# singleBandRepeater.net
KiCad netlist of a schematic drawn in EAGLE
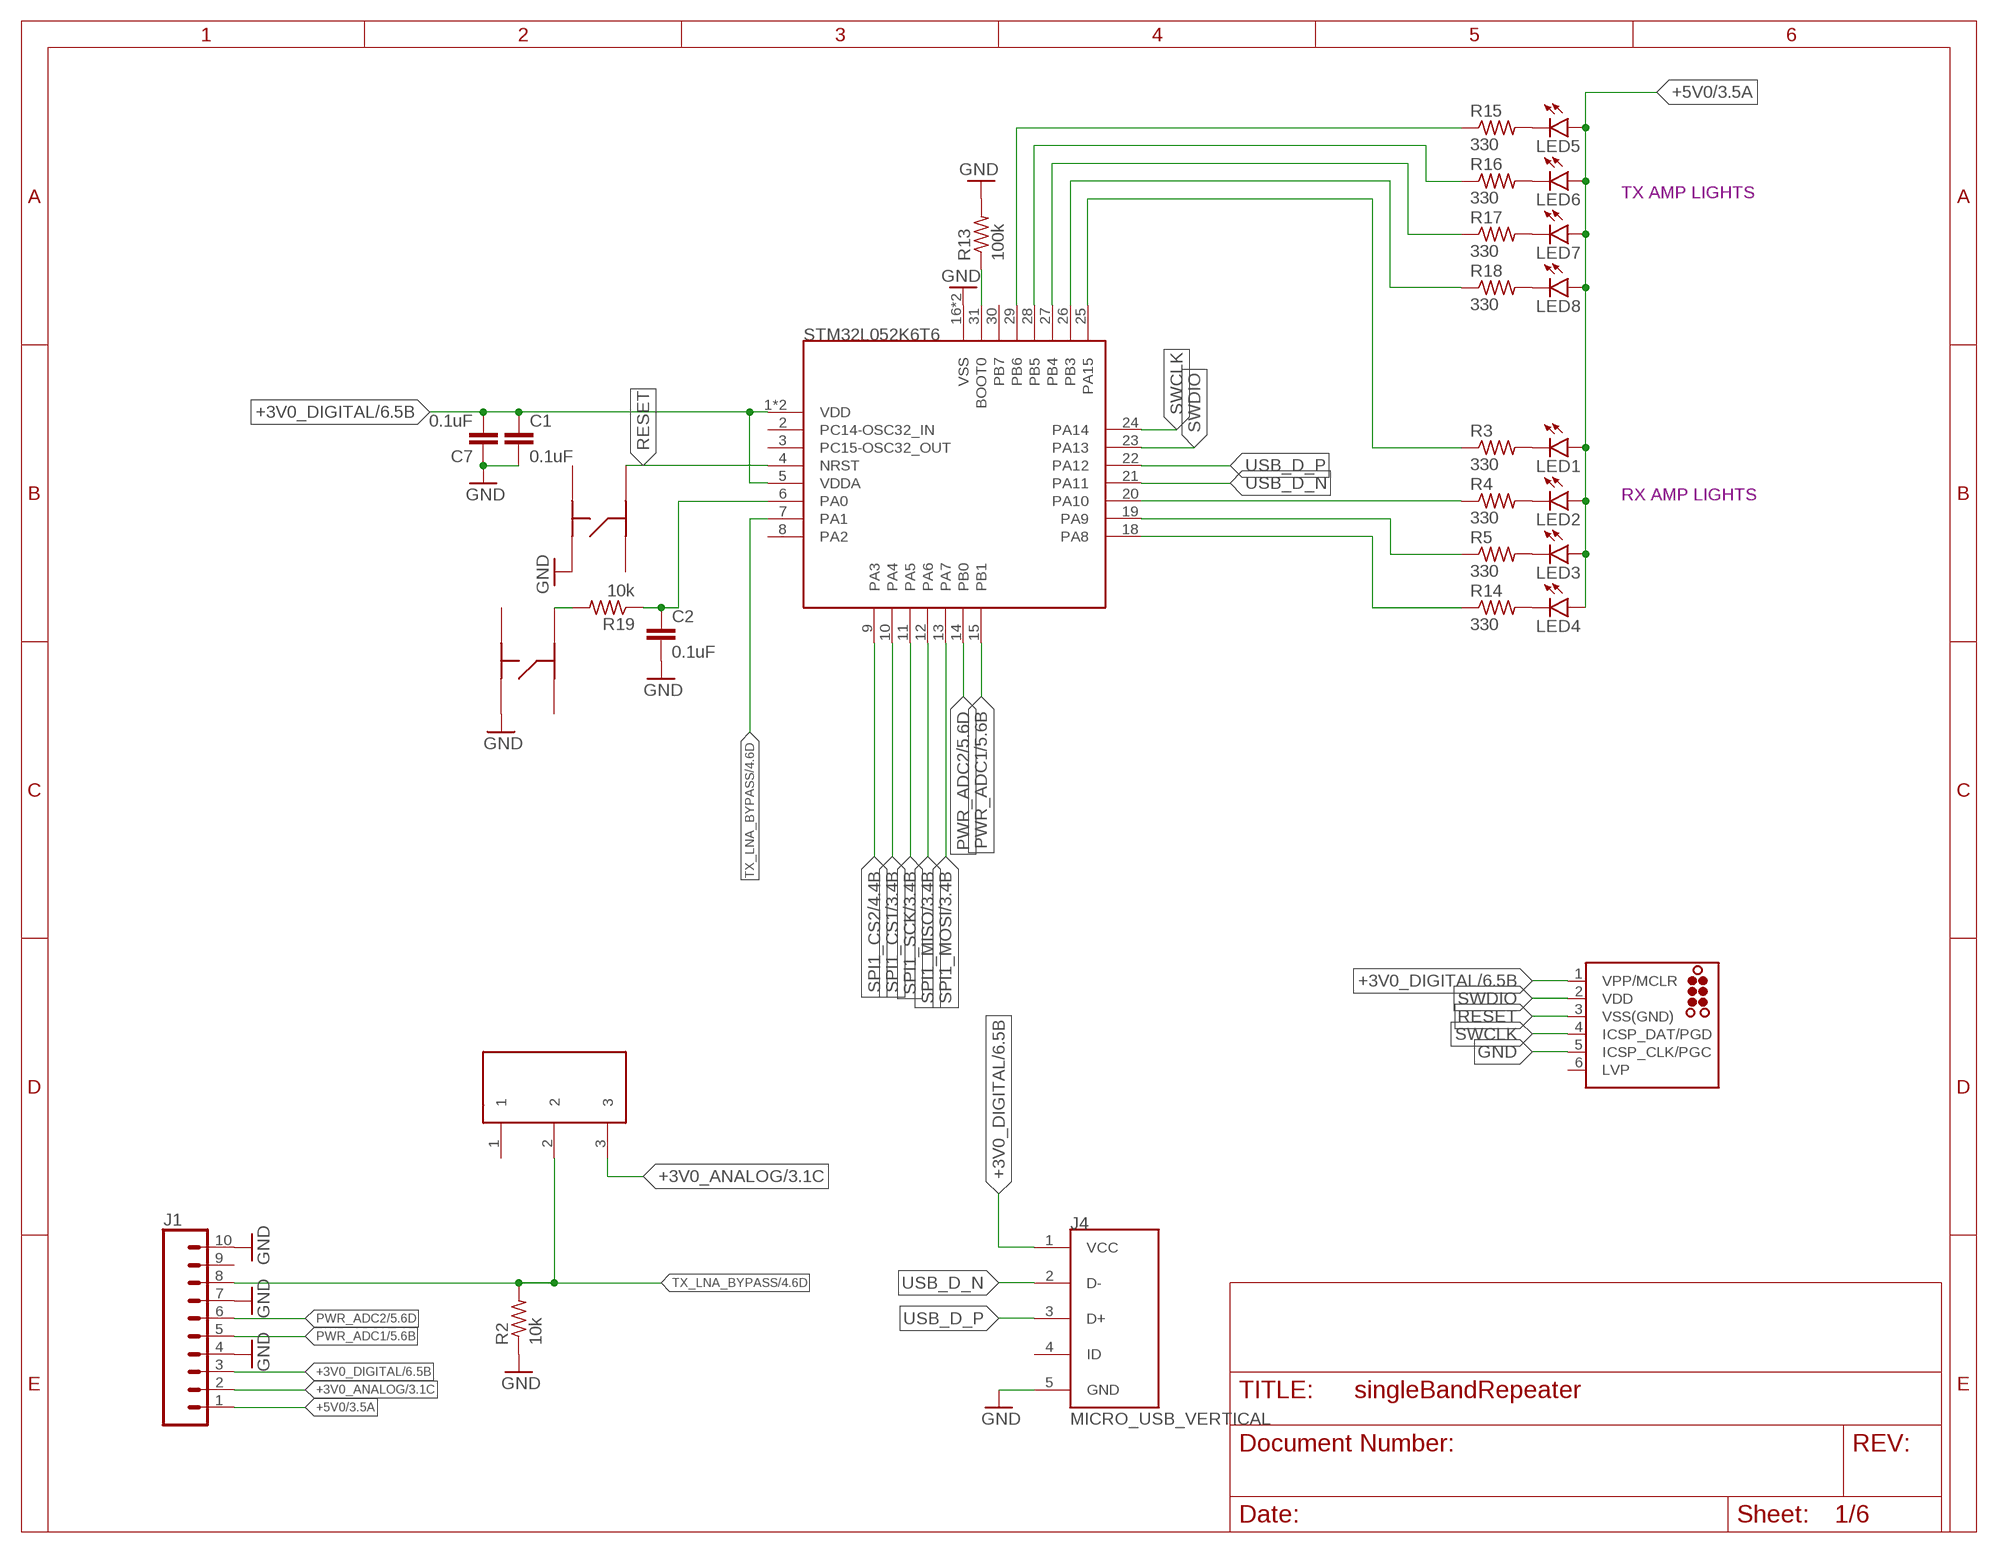
[diagram p0: schematic, sheet 1]
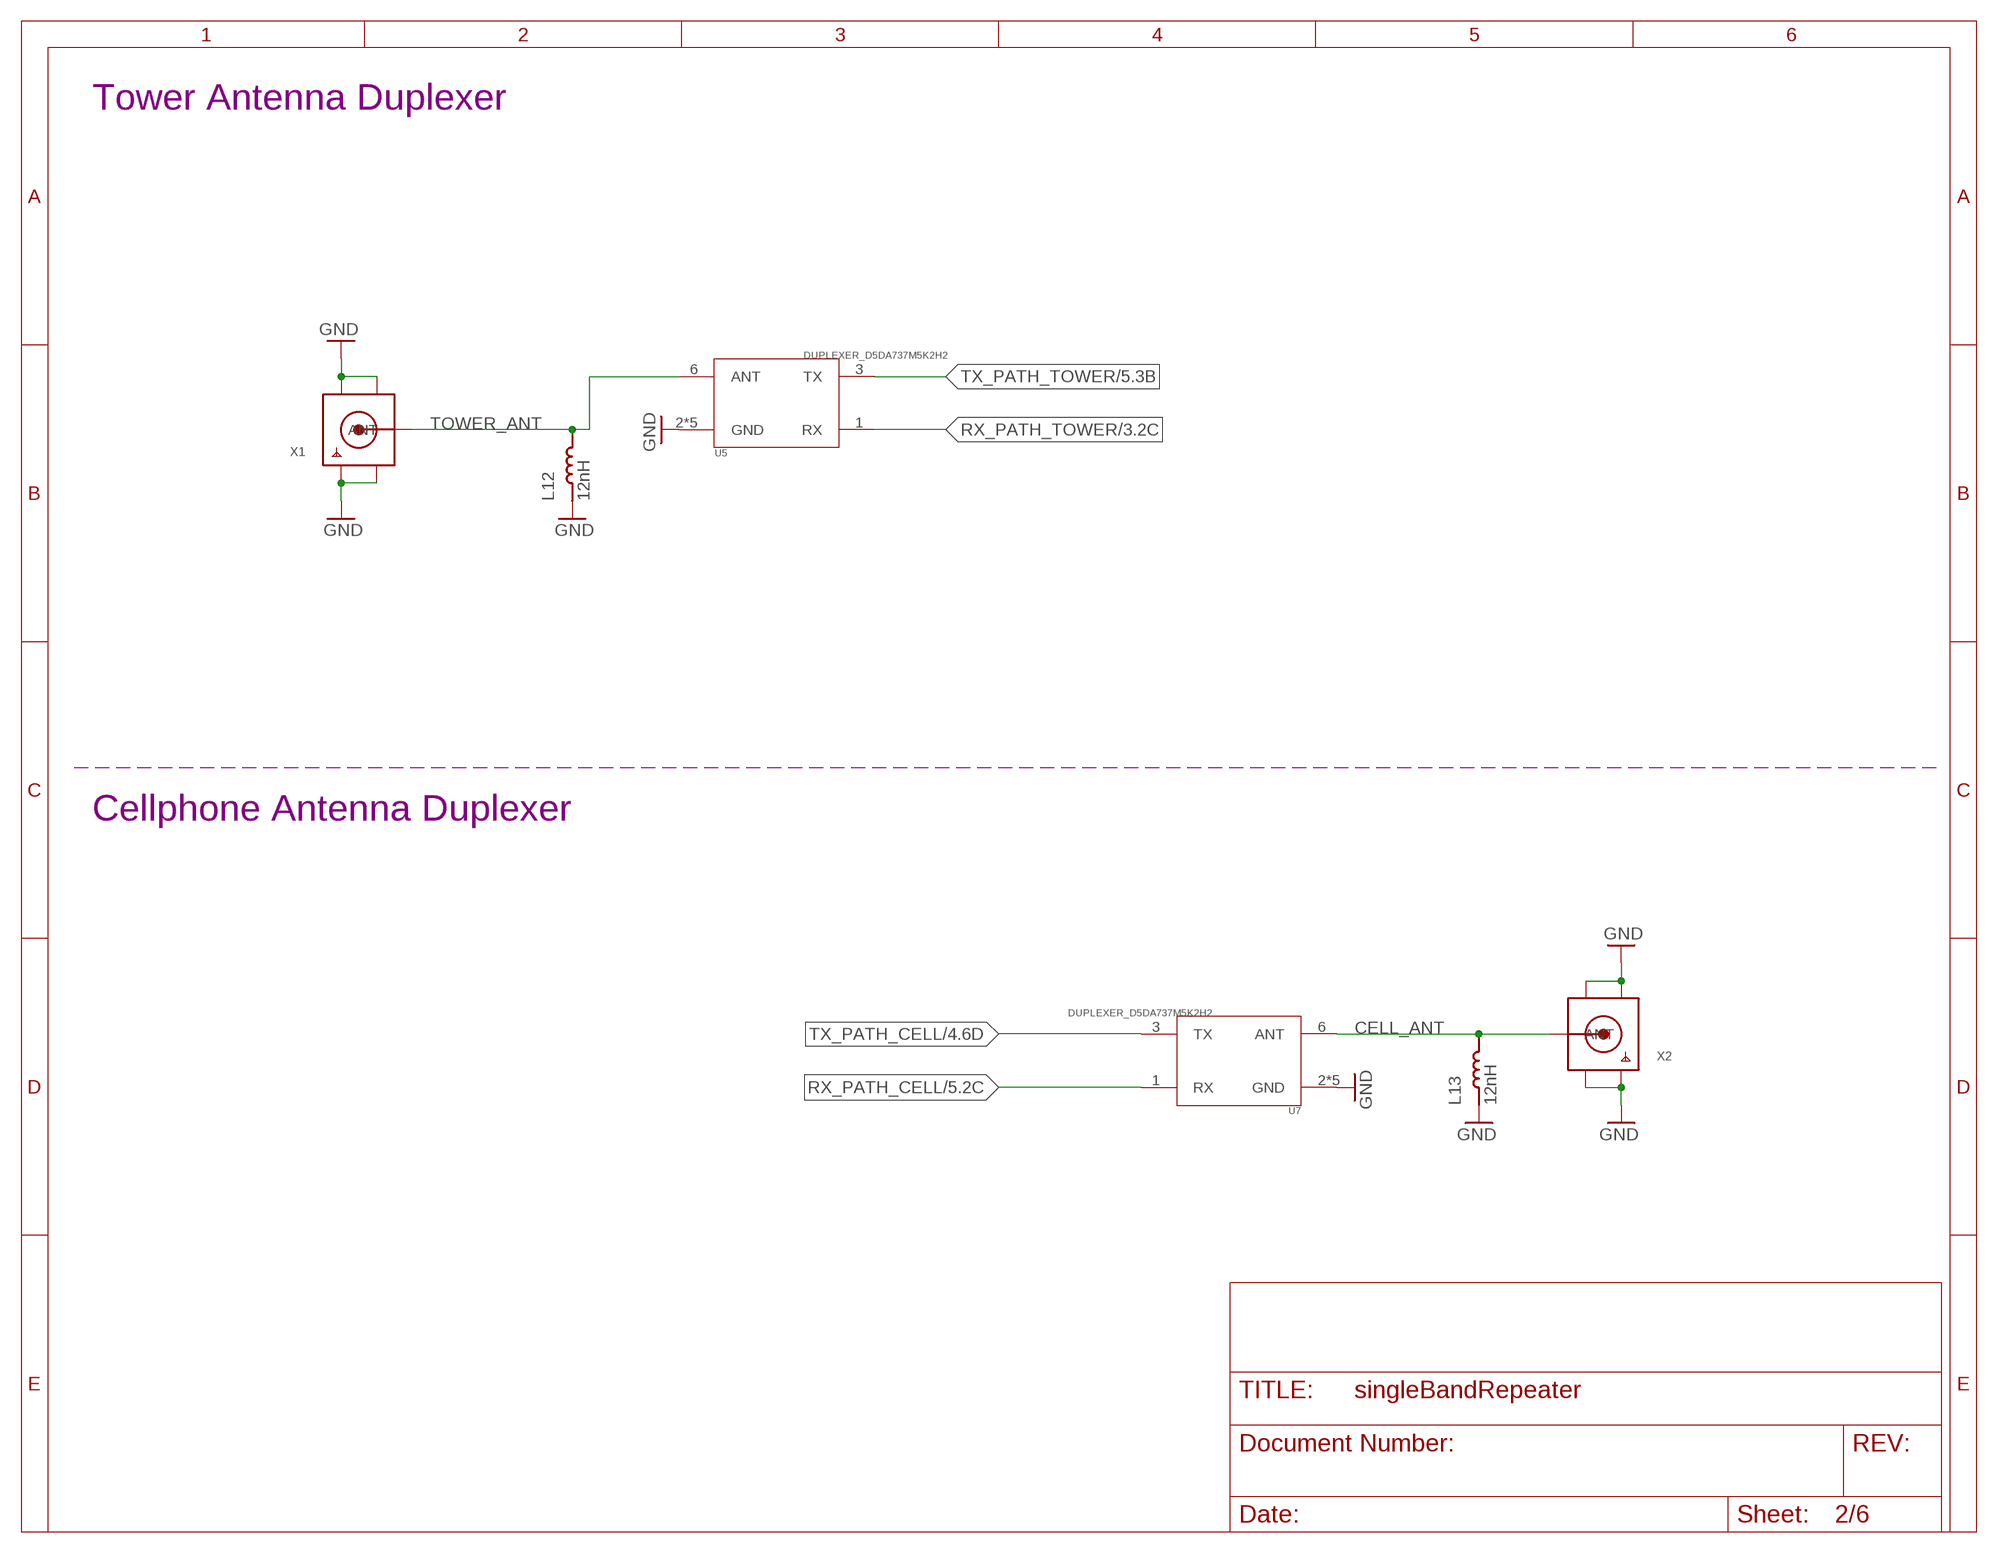
[diagram p1: schematic, sheet 2]
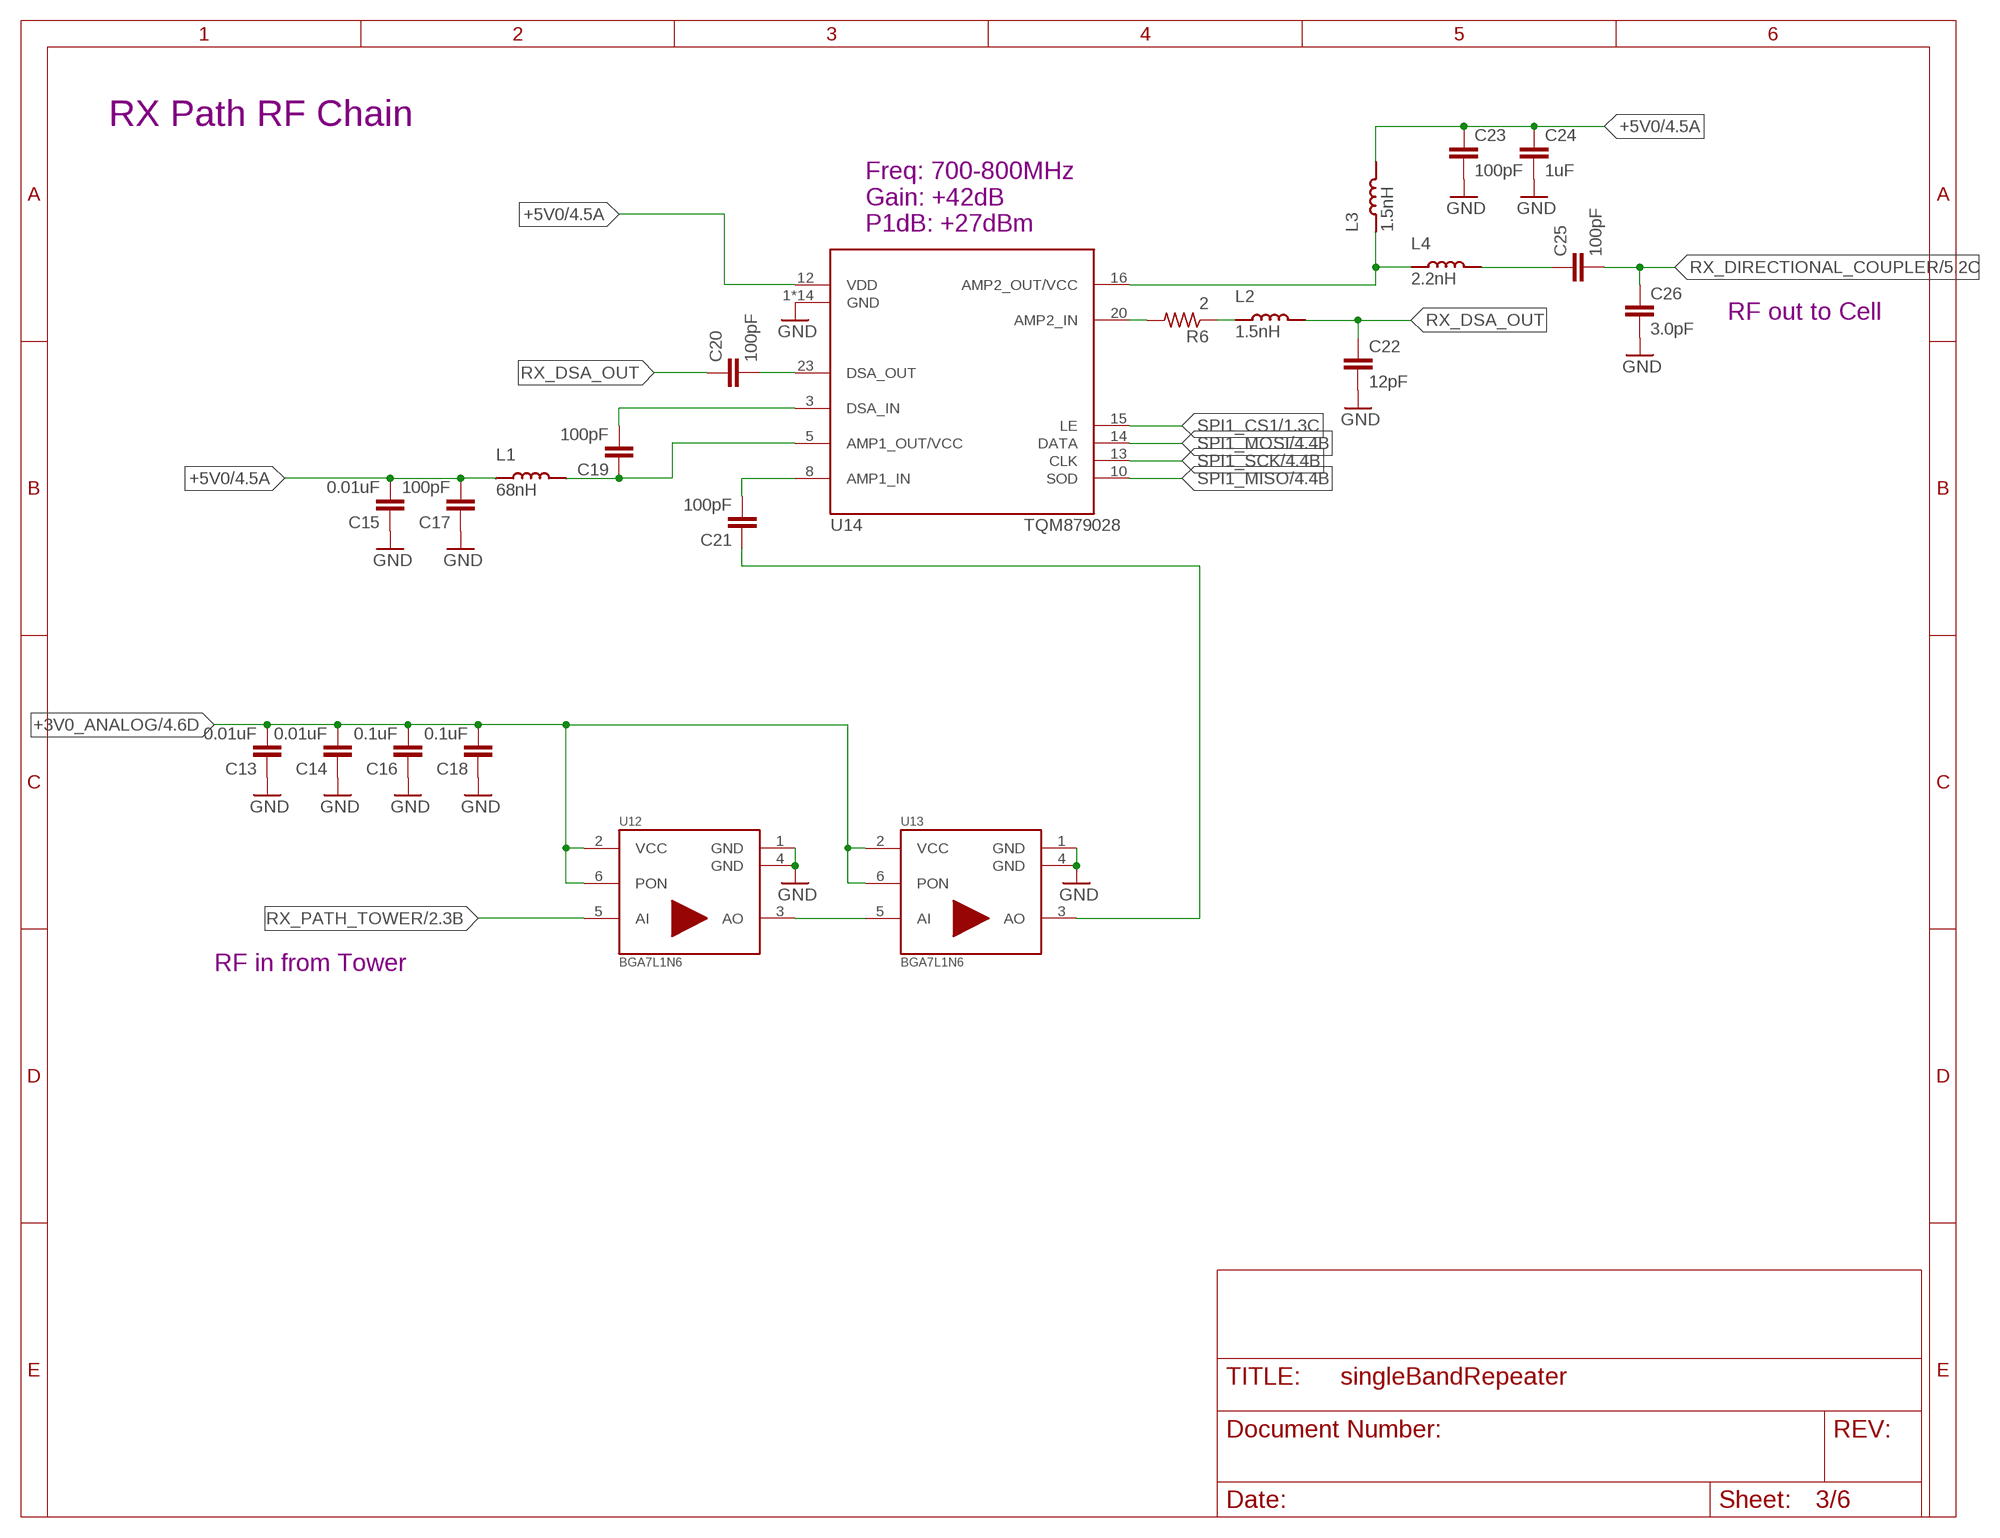
[diagram p2: schematic, sheet 3]
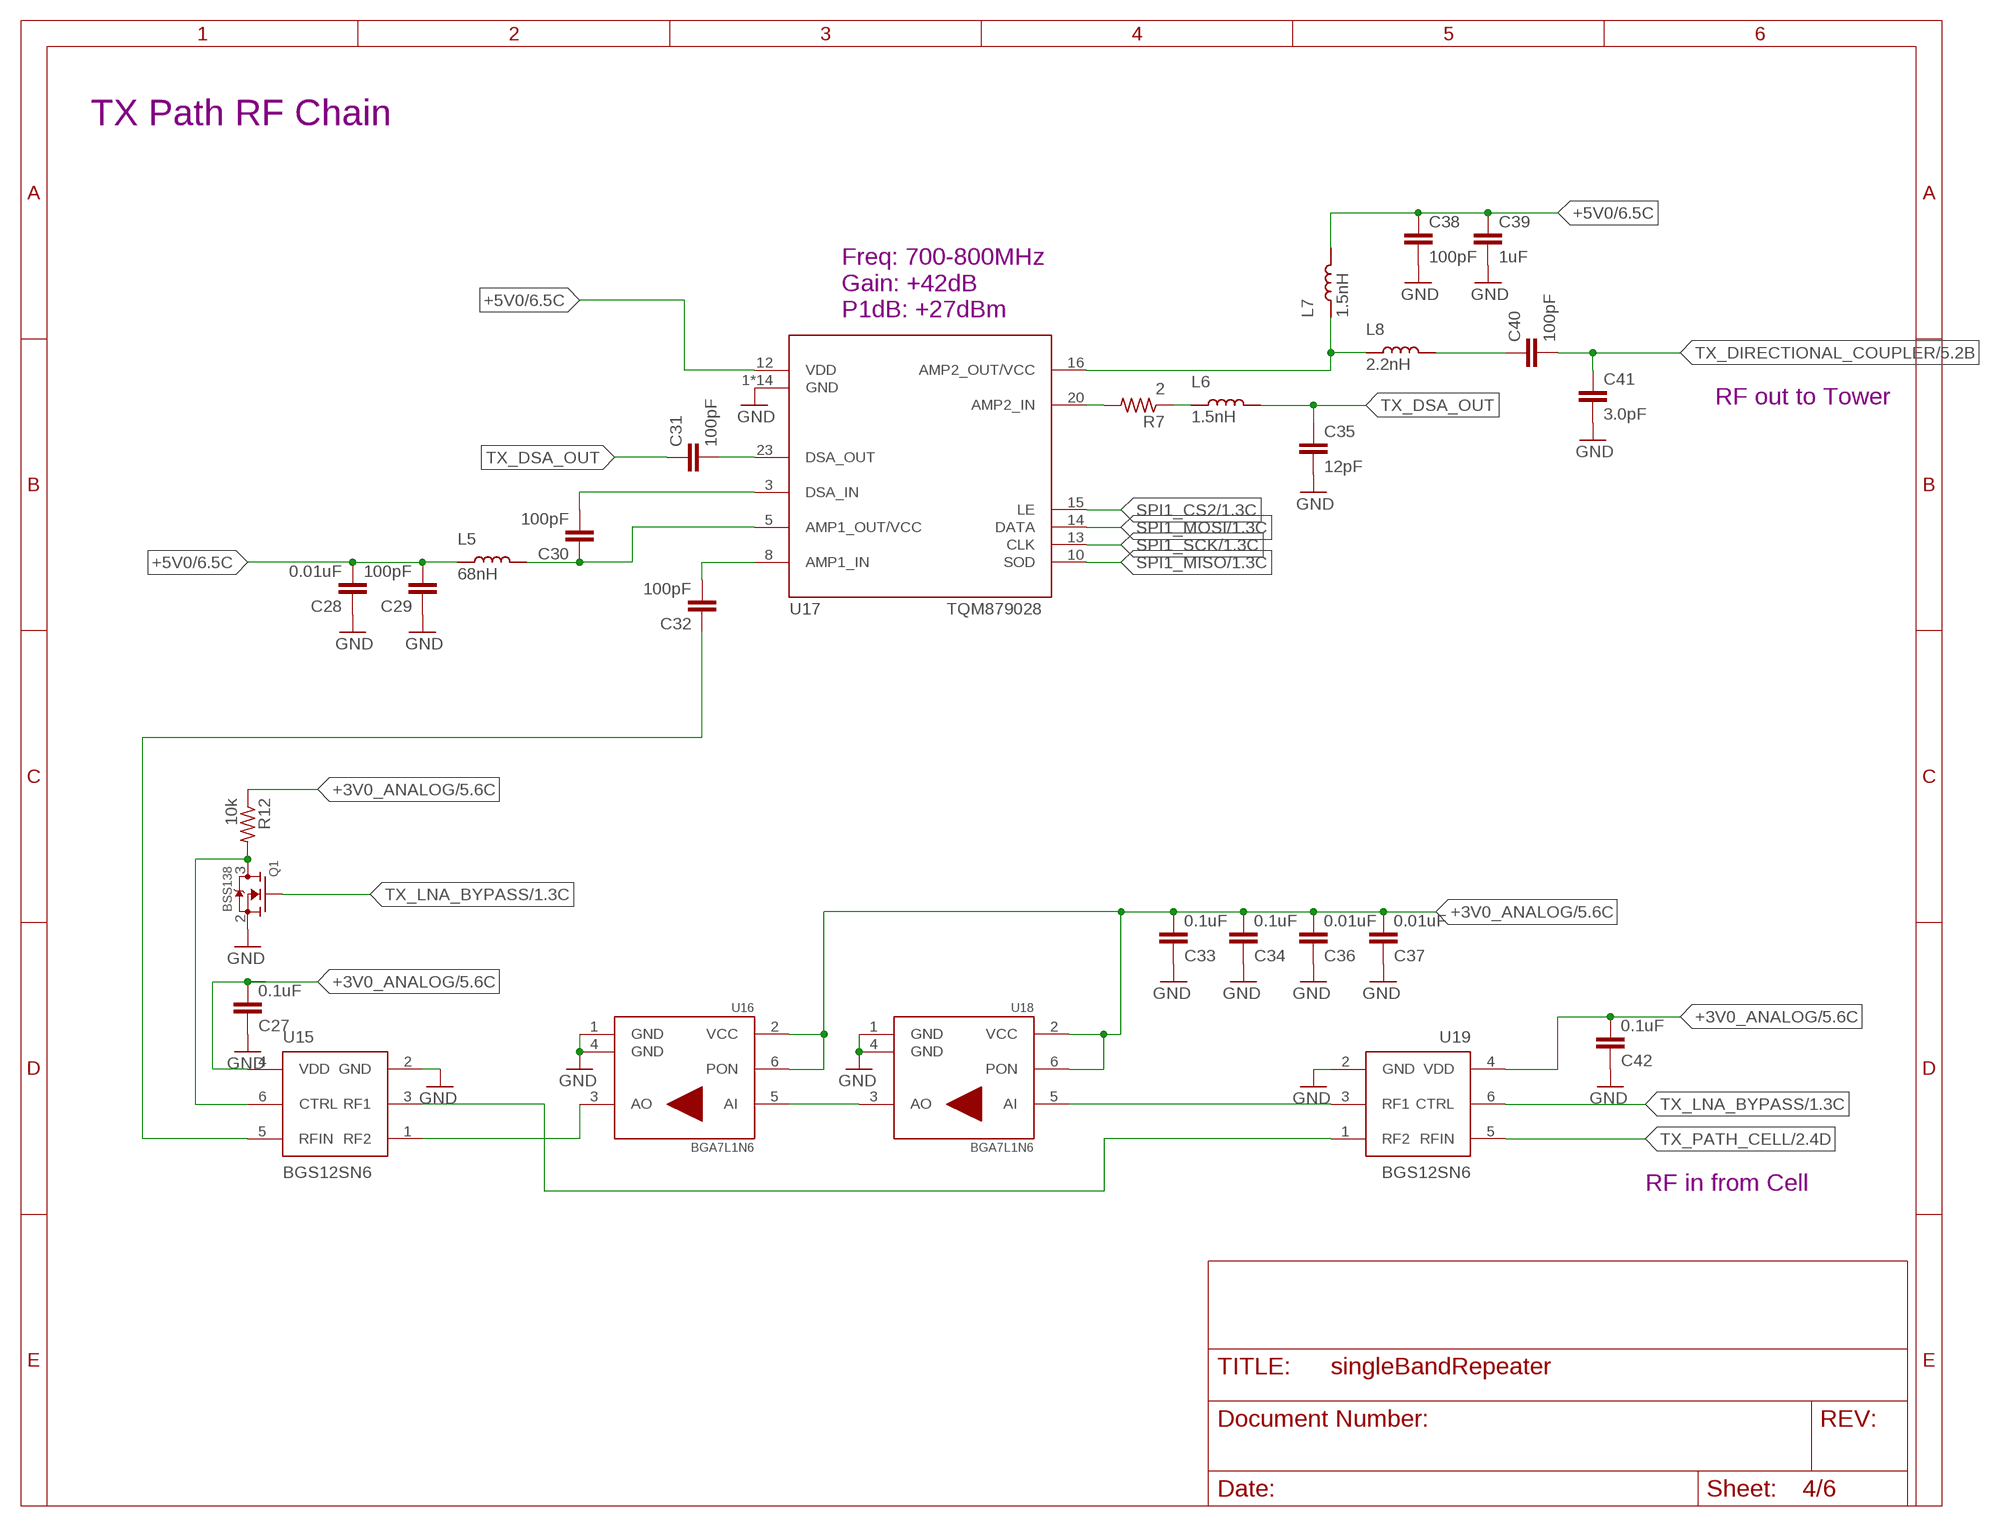
[diagram p3: schematic, sheet 4]
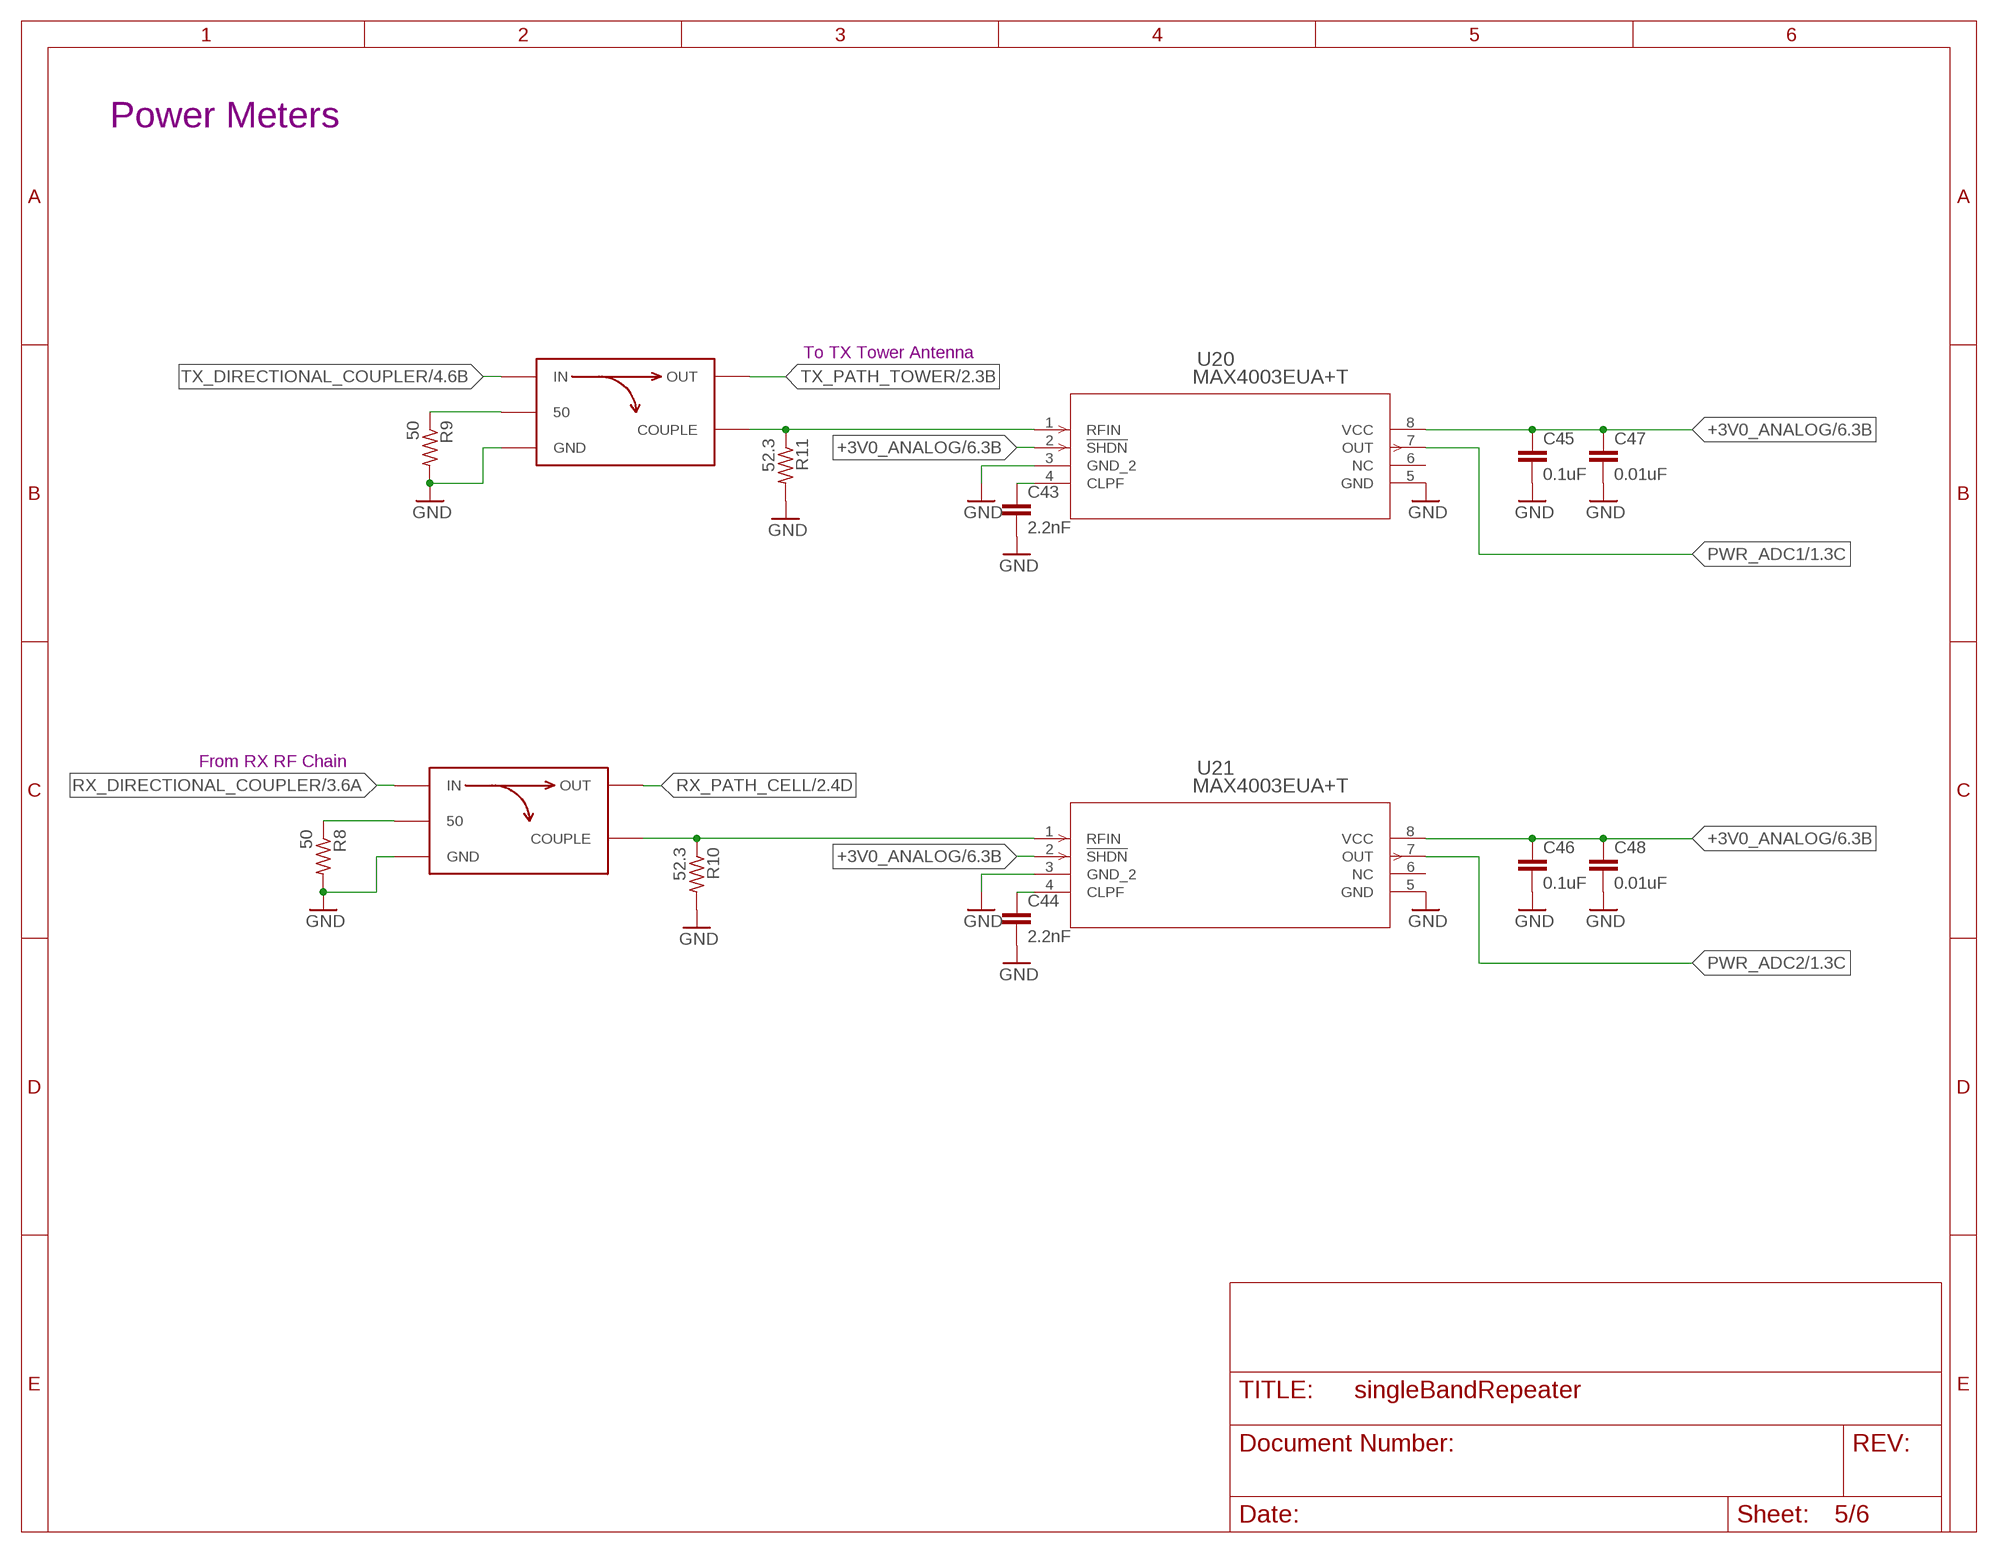
[diagram p4: schematic, sheet 5]
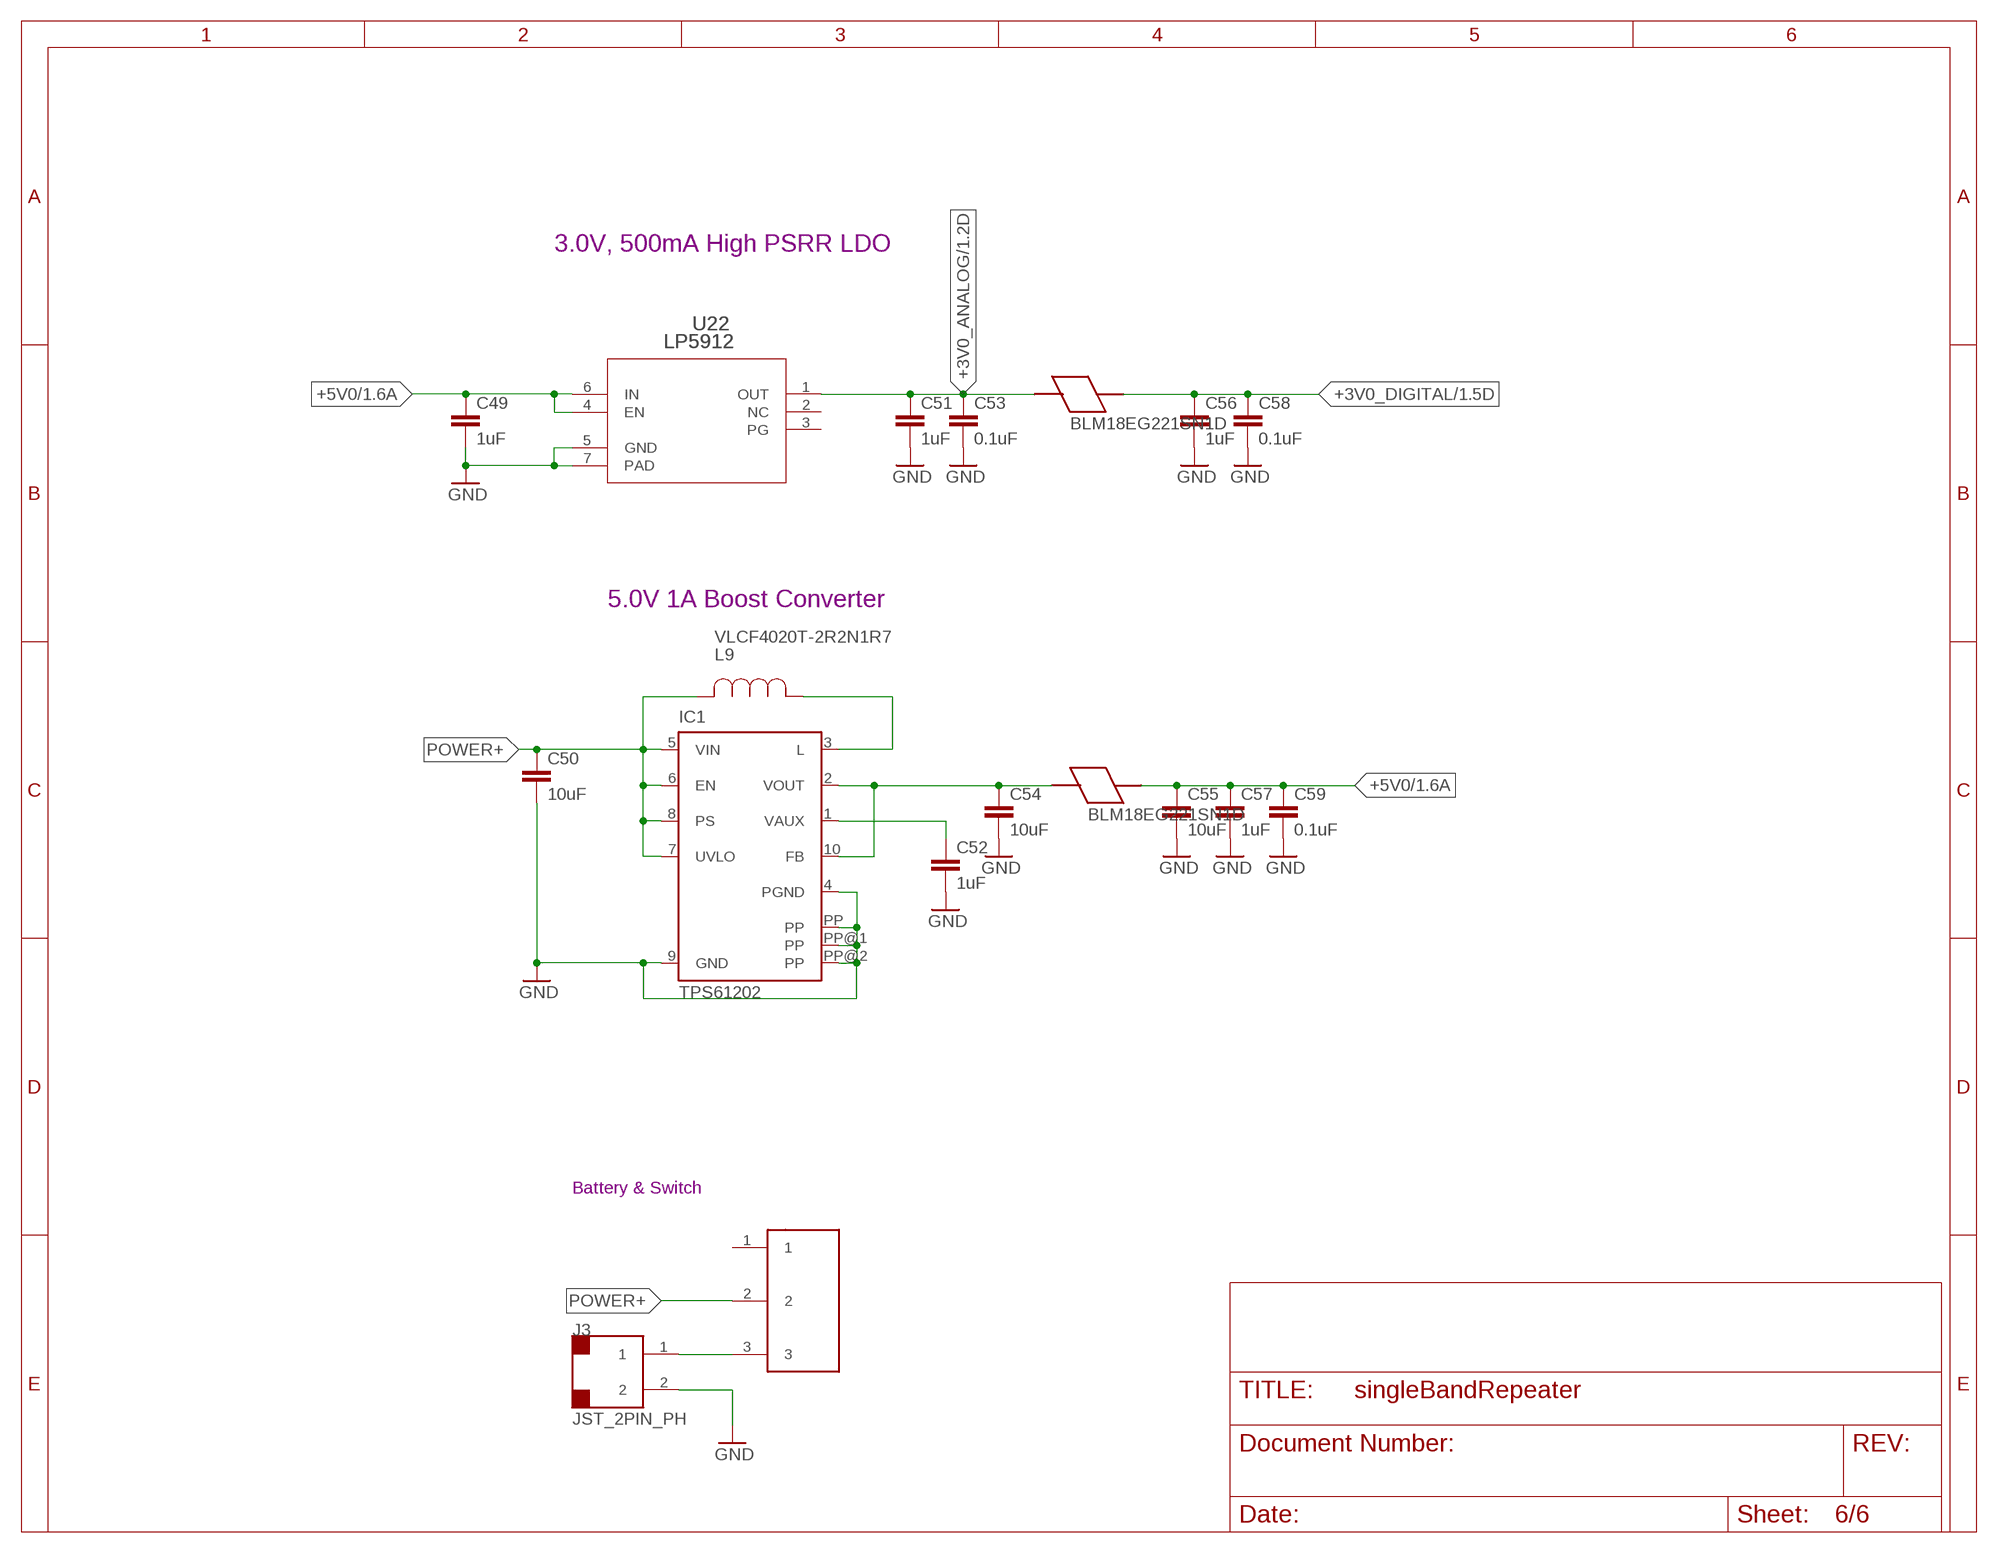
[diagram p5: schematic, sheet 6]

(export (version "E")
  (design (tool "Eeschema 10.0.6"))
  (components
    (comp (ref "C43")
      (value "2.2nF")
      (footprint "eagle-import:C0402")
      (libsource (lib "eagle-import") (part "C-EUC0402"))
    )
    (comp (ref "C44")
      (value "2.2nF")
      (footprint "eagle-import:C0402")
      (libsource (lib "eagle-import") (part "C-EUC0402"))
    )
    (comp (ref "C45")
      (value "0.1uF")
      (footprint "eagle-import:C0402")
      (libsource (lib "eagle-import") (part "C-EUC0402"))
    )
    (comp (ref "C46")
      (value "0.1uF")
      (footprint "eagle-import:C0402")
      (libsource (lib "eagle-import") (part "C-EUC0402"))
    )
    (comp (ref "C47")
      (value "0.01uF")
      (footprint "eagle-import:C0402")
      (libsource (lib "eagle-import") (part "C-EUC0402"))
    )
    (comp (ref "C48")
      (value "0.01uF")
      (footprint "eagle-import:C0402")
      (libsource (lib "eagle-import") (part "C-EUC0402"))
    )
    (comp (ref "HY1")
      (value "HHM22152A2")
      (footprint "eagle-import:HHM22152A2")
      (libsource (lib "eagle-import") (part "HHM22152A2"))
    )
    (comp (ref "HY2")
      (value "HHM22152A2")
      (footprint "eagle-import:HHM22152A2")
      (libsource (lib "eagle-import") (part "HHM22152A2"))
    )
    (comp (ref "R8")
      (value "50")
      (footprint "eagle-import:R0402")
      (libsource (lib "eagle-import") (part "R-US_R0402"))
    )
    (comp (ref "R9")
      (value "50")
      (footprint "eagle-import:R0402")
      (libsource (lib "eagle-import") (part "R-US_R0402"))
    )
    (comp (ref "R10")
      (value "52.3")
      (footprint "eagle-import:R0402")
      (libsource (lib "eagle-import") (part "R-US_R0402"))
    )
    (comp (ref "R11")
      (value "52.3")
      (footprint "eagle-import:R0402")
      (libsource (lib "eagle-import") (part "R-US_R0402"))
    )
    (comp (ref "U20")
      (value "MAX4003EUA+T")
      (footprint "eagle-import:21-0036K")
      (fields (field (name "MANUFACTURER_PART_NUMBER") "max4003eua+T"))
      (libsource (lib "eagle-import") (part "MAX4003EUA+T"))
    )
    (comp (ref "U21")
      (value "MAX4003EUA+T")
      (footprint "eagle-import:21-0036K")
      (fields (field (name "MANUFACTURER_PART_NUMBER") "max4003eua+T"))
      (libsource (lib "eagle-import") (part "MAX4003EUA+T"))
    )
    (comp (ref "L12")
      (value "12nH")
      (footprint "eagle-import:0402")
      (libsource (lib "eagle-import") (part "INDUCTOR0402"))
    )
    (comp (ref "L13")
      (value "12nH")
      (footprint "eagle-import:0402")
      (libsource (lib "eagle-import") (part "INDUCTOR0402"))
    )
    (comp (ref "U5")
      (value "DUPLEXER_D5DA737M5K2H2")
      (footprint "eagle-import:TAIYO_YUDEN_DUPLEX_1.8X1.4")
      (libsource (lib "eagle-import") (part "DUPLEXER_D5DA737M5K2H2"))
    )
    (comp (ref "U7")
      (value "DUPLEXER_D5DA737M5K2H2")
      (footprint "eagle-import:TAIYO_YUDEN_DUPLEX_1.8X1.4")
      (libsource (lib "eagle-import") (part "DUPLEXER_D5DA737M5K2H2"))
    )
    (comp (ref "X1")
      (value "SMACONNECTORSMA_DIP")
      (footprint "eagle-import:SMA_DIP")
      (libsource (lib "eagle-import") (part "SMACONNECTORSMA_DIP"))
    )
    (comp (ref "X2")
      (value "SMACONNECTORSMA_DIP")
      (footprint "eagle-import:SMA_DIP")
      (libsource (lib "eagle-import") (part "SMACONNECTORSMA_DIP"))
    )
    (comp (ref "C1")
      (value "0.1uF")
      (footprint "eagle-import:C0402")
      (libsource (lib "eagle-import") (part "C-EUC0402"))
    )
    (comp (ref "C2")
      (value "0.1uF")
      (footprint "eagle-import:C0402")
      (libsource (lib "eagle-import") (part "C-EUC0402"))
    )
    (comp (ref "C7")
      (value "0.1uF")
      (footprint "eagle-import:C0402")
      (libsource (lib "eagle-import") (part "C-EUC0402"))
    )
    (comp (ref "J1")
      (value "CONN_10\"")
      (footprint "eagle-import:1X10")
      (libsource (lib "eagle-import") (part "CONN_10{dblquote}"))
    )
    (comp (ref "J2")
      (value "TC2030-MCP")
      (footprint "eagle-import:TC2030-MCP")
      (libsource (lib "eagle-import") (part "TC2030-MCP"))
    )
    (comp (ref "J4")
      (value "MICRO_USB_VERTICAL")
      (footprint "eagle-import:MICRO_USB_VERTICAL")
      (libsource (lib "eagle-import") (part "MICRO_USB_VERTICAL"))
    )
    (comp (ref "LED1")
      (value "LEDCHIPLED_0603")
      (footprint "eagle-import:CHIPLED_0603")
      (libsource (lib "eagle-import") (part "LEDCHIPLED_0603"))
    )
    (comp (ref "LED2")
      (value "LEDCHIPLED_0603")
      (footprint "eagle-import:CHIPLED_0603")
      (libsource (lib "eagle-import") (part "LEDCHIPLED_0603"))
    )
    (comp (ref "LED3")
      (value "LEDCHIPLED_0603")
      (footprint "eagle-import:CHIPLED_0603")
      (libsource (lib "eagle-import") (part "LEDCHIPLED_0603"))
    )
    (comp (ref "LED4")
      (value "LEDCHIPLED_0603")
      (footprint "eagle-import:CHIPLED_0603")
      (libsource (lib "eagle-import") (part "LEDCHIPLED_0603"))
    )
    (comp (ref "LED5")
      (value "LEDCHIPLED_0603")
      (footprint "eagle-import:CHIPLED_0603")
      (libsource (lib "eagle-import") (part "LEDCHIPLED_0603"))
    )
    (comp (ref "LED6")
      (value "LEDCHIPLED_0603")
      (footprint "eagle-import:CHIPLED_0603")
      (libsource (lib "eagle-import") (part "LEDCHIPLED_0603"))
    )
    (comp (ref "LED7")
      (value "LEDCHIPLED_0603")
      (footprint "eagle-import:CHIPLED_0603")
      (libsource (lib "eagle-import") (part "LEDCHIPLED_0603"))
    )
    (comp (ref "LED8")
      (value "LEDCHIPLED_0603")
      (footprint "eagle-import:CHIPLED_0603")
      (libsource (lib "eagle-import") (part "LEDCHIPLED_0603"))
    )
    (comp (ref "R2")
      (value "10k")
      (footprint "eagle-import:R0402")
      (libsource (lib "eagle-import") (part "R-US_R0402"))
    )
    (comp (ref "R3")
      (value "330")
      (footprint "eagle-import:R0402")
      (libsource (lib "eagle-import") (part "R-US_R0402"))
    )
    (comp (ref "R4")
      (value "330")
      (footprint "eagle-import:R0402")
      (libsource (lib "eagle-import") (part "R-US_R0402"))
    )
    (comp (ref "R5")
      (value "330")
      (footprint "eagle-import:R0402")
      (libsource (lib "eagle-import") (part "R-US_R0402"))
    )
    (comp (ref "R13")
      (value "100k")
      (footprint "eagle-import:R0402")
      (libsource (lib "eagle-import") (part "R-US_R0402"))
    )
    (comp (ref "R14")
      (value "330")
      (footprint "eagle-import:R0402")
      (libsource (lib "eagle-import") (part "R-US_R0402"))
    )
    (comp (ref "R15")
      (value "330")
      (footprint "eagle-import:R0402")
      (libsource (lib "eagle-import") (part "R-US_R0402"))
    )
    (comp (ref "R16")
      (value "330")
      (footprint "eagle-import:R0402")
      (libsource (lib "eagle-import") (part "R-US_R0402"))
    )
    (comp (ref "R17")
      (value "330")
      (footprint "eagle-import:R0402")
      (libsource (lib "eagle-import") (part "R-US_R0402"))
    )
    (comp (ref "R18")
      (value "330")
      (footprint "eagle-import:R0402")
      (libsource (lib "eagle-import") (part "R-US_R0402"))
    )
    (comp (ref "R19")
      (value "10k")
      (footprint "eagle-import:R0402")
      (libsource (lib "eagle-import") (part "R-US_R0402"))
    )
    (comp (ref "S1")
      (value "KMR731NG")
      (footprint "eagle-import:KMR731NG")
      (libsource (lib "eagle-import") (part "KMR731NG"))
    )
    (comp (ref "S3")
      (value "SPDT_THRU")
      (footprint "eagle-import:SPDT_THRU")
      (libsource (lib "eagle-import") (part "SPDT_THRU"))
    )
    (comp (ref "S5")
      (value "KMR731NG")
      (footprint "eagle-import:KMR731NG")
      (libsource (lib "eagle-import") (part "KMR731NG"))
    )
    (comp (ref "U2")
      (value "STM32L052K6T6LQFP32-7X7")
      (footprint "eagle-import:QFP80P900X900X160-32")
      (libsource (lib "eagle-import") (part "STM32L052K6T6LQFP32-7X7"))
    )
    (comp (ref "C27")
      (value "0.1uF")
      (footprint "eagle-import:C0402")
      (libsource (lib "eagle-import") (part "C-EUC0402"))
    )
    (comp (ref "C28")
      (value "0.01uF")
      (footprint "eagle-import:C0402")
      (libsource (lib "eagle-import") (part "C-EUC0402"))
    )
    (comp (ref "C29")
      (value "100pF")
      (footprint "eagle-import:C0402")
      (libsource (lib "eagle-import") (part "C-EUC0402"))
    )
    (comp (ref "C30")
      (value "100pF")
      (footprint "eagle-import:C0402")
      (libsource (lib "eagle-import") (part "C-EUC0402"))
    )
    (comp (ref "C31")
      (value "100pF")
      (footprint "eagle-import:C0402")
      (libsource (lib "eagle-import") (part "C-EUC0402"))
    )
    (comp (ref "C32")
      (value "100pF")
      (footprint "eagle-import:C0402")
      (libsource (lib "eagle-import") (part "C-EUC0402"))
    )
    (comp (ref "C33")
      (value "0.1uF")
      (footprint "eagle-import:C0402")
      (libsource (lib "eagle-import") (part "C-EUC0402"))
    )
    (comp (ref "C34")
      (value "0.1uF")
      (footprint "eagle-import:C0402")
      (libsource (lib "eagle-import") (part "C-EUC0402"))
    )
    (comp (ref "C35")
      (value "12pF")
      (footprint "eagle-import:C0402")
      (libsource (lib "eagle-import") (part "C-EUC0402"))
    )
    (comp (ref "C36")
      (value "0.01uF")
      (footprint "eagle-import:C0402")
      (libsource (lib "eagle-import") (part "C-EUC0402"))
    )
    (comp (ref "C37")
      (value "0.01uF")
      (footprint "eagle-import:C0402")
      (libsource (lib "eagle-import") (part "C-EUC0402"))
    )
    (comp (ref "C38")
      (value "100pF")
      (footprint "eagle-import:C0402")
      (libsource (lib "eagle-import") (part "C-EUC0402"))
    )
    (comp (ref "C39")
      (value "1uF")
      (footprint "eagle-import:C0402")
      (libsource (lib "eagle-import") (part "C-EUC0402"))
    )
    (comp (ref "C40")
      (value "100pF")
      (footprint "eagle-import:C0402")
      (libsource (lib "eagle-import") (part "C-EUC0402"))
    )
    (comp (ref "C41")
      (value "3.0pF")
      (footprint "eagle-import:C0402")
      (libsource (lib "eagle-import") (part "C-EUC0402"))
    )
    (comp (ref "C42")
      (value "0.1uF")
      (footprint "eagle-import:C0402")
      (libsource (lib "eagle-import") (part "C-EUC0402"))
    )
    (comp (ref "L5")
      (value "68nH")
      (footprint "eagle-import:0402")
      (libsource (lib "eagle-import") (part "INDUCTOR0402"))
    )
    (comp (ref "L6")
      (value "1.5nH")
      (footprint "eagle-import:0402")
      (libsource (lib "eagle-import") (part "INDUCTOR0402"))
    )
    (comp (ref "L7")
      (value "1.5nH")
      (footprint "eagle-import:0402")
      (libsource (lib "eagle-import") (part "INDUCTOR0402"))
    )
    (comp (ref "L8")
      (value "2.2nH")
      (footprint "eagle-import:0402")
      (libsource (lib "eagle-import") (part "INDUCTOR0402"))
    )
    (comp (ref "Q1")
      (value "BSS138")
      (footprint "eagle-import:SOT23-3")
      (libsource (lib "eagle-import") (part "BSS138"))
    )
    (comp (ref "R7")
      (value "2")
      (footprint "eagle-import:R0402")
      (libsource (lib "eagle-import") (part "R-US_R0402"))
    )
    (comp (ref "R12")
      (value "10k")
      (footprint "eagle-import:R0402")
      (libsource (lib "eagle-import") (part "R-US_R0402"))
    )
    (comp (ref "U15")
      (value "BGS12SN6")
      (footprint "eagle-import:INF-PG-TSNP-6-2")
      (libsource (lib "eagle-import") (part "BGS12SN6"))
    )
    (comp (ref "U16")
      (value "BGA7L1N6")
      (footprint "eagle-import:INF-PG-TSNP-6-2")
      (libsource (lib "eagle-import") (part "BGA7L1N6"))
    )
    (comp (ref "U17")
      (value "TQM879028")
      (footprint "eagle-import:QFN50P400X400X100-25T270N")
      (libsource (lib "eagle-import") (part "TQM879028"))
    )
    (comp (ref "U18")
      (value "BGA7L1N6")
      (footprint "eagle-import:INF-PG-TSNP-6-2")
      (libsource (lib "eagle-import") (part "BGA7L1N6"))
    )
    (comp (ref "U19")
      (value "BGS12SN6")
      (footprint "eagle-import:INF-PG-TSNP-6-2")
      (libsource (lib "eagle-import") (part "BGS12SN6"))
    )
    (comp (ref "C49")
      (value "1uF")
      (footprint "eagle-import:C0402")
      (libsource (lib "eagle-import") (part "C-EUC0402"))
    )
    (comp (ref "C50")
      (value "10uF")
      (footprint "eagle-import:C0805")
      (libsource (lib "eagle-import") (part "C-EUC0805"))
    )
    (comp (ref "C51")
      (value "1uF")
      (footprint "eagle-import:C0402")
      (libsource (lib "eagle-import") (part "C-EUC0402"))
    )
    (comp (ref "C52")
      (value "1uF")
      (footprint "eagle-import:C0402")
      (libsource (lib "eagle-import") (part "C-EUC0402"))
    )
    (comp (ref "C53")
      (value "0.1uF")
      (footprint "eagle-import:C0402")
      (libsource (lib "eagle-import") (part "C-EUC0402"))
    )
    (comp (ref "C54")
      (value "10uF")
      (footprint "eagle-import:C0805")
      (libsource (lib "eagle-import") (part "C-EUC0805"))
    )
    (comp (ref "C55")
      (value "10uF")
      (footprint "eagle-import:C0805")
      (libsource (lib "eagle-import") (part "C-EUC0805"))
    )
    (comp (ref "C56")
      (value "1uF")
      (footprint "eagle-import:C0402")
      (libsource (lib "eagle-import") (part "C-EUC0402"))
    )
    (comp (ref "C57")
      (value "1uF")
      (footprint "eagle-import:C0402")
      (libsource (lib "eagle-import") (part "C-EUC0402"))
    )
    (comp (ref "C58")
      (value "0.1uF")
      (footprint "eagle-import:C0402")
      (libsource (lib "eagle-import") (part "C-EUC0402"))
    )
    (comp (ref "C59")
      (value "0.1uF")
      (footprint "eagle-import:C0402")
      (libsource (lib "eagle-import") (part "C-EUC0402"))
    )
    (comp (ref "IC1")
      (value "TPS61202")
      (footprint "eagle-import:S-PDSO-N10")
      (fields (field (name "MPN") "TPS61202DRCR"))
      (libsource (lib "eagle-import") (part "TPS61202"))
    )
    (comp (ref "J3")
      (value "JST_2PIN_PH")
      (footprint "eagle-import:JST_2PIN_PH")
      (libsource (lib "eagle-import") (part "JST_2PIN_PH"))
    )
    (comp (ref "L9")
      (value "VLCF4020T-2R2N1R7")
      (footprint "eagle-import:IND_4028")
      (libsource (lib "eagle-import") (part "VLCF4020T-2R2N1R7"))
    )
    (comp (ref "L10")
      (value "BLM18EG221SN1D")
      (footprint "eagle-import:IND_BLM18_0603")
      (fields (field (name "COPYRIGHT") "Copyright C 2015 Accelerated Designs. All rights reserved"))
      (libsource (lib "eagle-import") (part "BLM18EG221SN1D"))
    )
    (comp (ref "L11")
      (value "BLM18EG221SN1D")
      (footprint "eagle-import:IND_BLM18_0603")
      (fields (field (name "COPYRIGHT") "Copyright C 2015 Accelerated Designs. All rights reserved"))
      (libsource (lib "eagle-import") (part "BLM18EG221SN1D"))
    )
    (comp (ref "S4")
      (value "SPDT_THRU")
      (footprint "eagle-import:SPDT_THRU")
      (libsource (lib "eagle-import") (part "SPDT_THRU"))
    )
    (comp (ref "U22")
      (value "LP5912")
      (footprint "eagle-import:DRV0006A")
      (libsource (lib "eagle-import") (part "LP5912"))
    )
    (comp (ref "C13")
      (value "0.01uF")
      (footprint "eagle-import:C0402")
      (libsource (lib "eagle-import") (part "C-EUC0402"))
    )
    (comp (ref "C14")
      (value "0.01uF")
      (footprint "eagle-import:C0402")
      (libsource (lib "eagle-import") (part "C-EUC0402"))
    )
    (comp (ref "C15")
      (value "0.01uF")
      (footprint "eagle-import:C0402")
      (libsource (lib "eagle-import") (part "C-EUC0402"))
    )
    (comp (ref "C16")
      (value "0.1uF")
      (footprint "eagle-import:C0402")
      (libsource (lib "eagle-import") (part "C-EUC0402"))
    )
    (comp (ref "C17")
      (value "100pF")
      (footprint "eagle-import:C0402")
      (libsource (lib "eagle-import") (part "C-EUC0402"))
    )
    (comp (ref "C18")
      (value "0.1uF")
      (footprint "eagle-import:C0402")
      (libsource (lib "eagle-import") (part "C-EUC0402"))
    )
    (comp (ref "C19")
      (value "100pF")
      (footprint "eagle-import:C0402")
      (libsource (lib "eagle-import") (part "C-EUC0402"))
    )
    (comp (ref "C20")
      (value "100pF")
      (footprint "eagle-import:C0402")
      (libsource (lib "eagle-import") (part "C-EUC0402"))
    )
    (comp (ref "C21")
      (value "100pF")
      (footprint "eagle-import:C0402")
      (libsource (lib "eagle-import") (part "C-EUC0402"))
    )
    (comp (ref "C22")
      (value "12pF")
      (footprint "eagle-import:C0402")
      (libsource (lib "eagle-import") (part "C-EUC0402"))
    )
    (comp (ref "C23")
      (value "100pF")
      (footprint "eagle-import:C0402")
      (libsource (lib "eagle-import") (part "C-EUC0402"))
    )
    (comp (ref "C24")
      (value "1uF")
      (footprint "eagle-import:C0402")
      (libsource (lib "eagle-import") (part "C-EUC0402"))
    )
    (comp (ref "C25")
      (value "100pF")
      (footprint "eagle-import:C0402")
      (libsource (lib "eagle-import") (part "C-EUC0402"))
    )
    (comp (ref "C26")
      (value "3.0pF")
      (footprint "eagle-import:C0402")
      (libsource (lib "eagle-import") (part "C-EUC0402"))
    )
    (comp (ref "L1")
      (value "68nH")
      (footprint "eagle-import:0402")
      (libsource (lib "eagle-import") (part "INDUCTOR0402"))
    )
    (comp (ref "L2")
      (value "1.5nH")
      (footprint "eagle-import:0402")
      (libsource (lib "eagle-import") (part "INDUCTOR0402"))
    )
    (comp (ref "L3")
      (value "1.5nH")
      (footprint "eagle-import:0402")
      (libsource (lib "eagle-import") (part "INDUCTOR0402"))
    )
    (comp (ref "L4")
      (value "2.2nH")
      (footprint "eagle-import:0402")
      (libsource (lib "eagle-import") (part "INDUCTOR0402"))
    )
    (comp (ref "R6")
      (value "2")
      (footprint "eagle-import:R0402")
      (libsource (lib "eagle-import") (part "R-US_R0402"))
    )
    (comp (ref "U12")
      (value "BGA7L1N6")
      (footprint "eagle-import:INF-PG-TSNP-6-2")
      (libsource (lib "eagle-import") (part "BGA7L1N6"))
    )
    (comp (ref "U13")
      (value "BGA7L1N6")
      (footprint "eagle-import:INF-PG-TSNP-6-2")
      (libsource (lib "eagle-import") (part "BGA7L1N6"))
    )
    (comp (ref "U14")
      (value "TQM879028")
      (footprint "eagle-import:QFN50P400X400X100-25T270N")
      (libsource (lib "eagle-import") (part "TQM879028"))
    )
  )
  (nets
    (net (code "1") (name "+3V0_ANALOG") (class "Default")
      (node (ref "C13") (pin "2") (pinfunction "2_2") (pintype "passive"))
      (node (ref "C14") (pin "2") (pinfunction "2_2") (pintype "passive"))
      (node (ref "C16") (pin "2") (pinfunction "2_2") (pintype "passive"))
      (node (ref "C18") (pin "2") (pinfunction "2_2") (pintype "passive"))
      (node (ref "C27") (pin "2") (pinfunction "2_2") (pintype "passive"))
      (node (ref "C33") (pin "2") (pinfunction "2_2") (pintype "passive"))
      (node (ref "C34") (pin "2") (pinfunction "2_2") (pintype "passive"))
      (node (ref "C36") (pin "2") (pinfunction "2_2") (pintype "passive"))
      (node (ref "C37") (pin "2") (pinfunction "2_2") (pintype "passive"))
      (node (ref "C42") (pin "2") (pinfunction "2_2") (pintype "passive"))
      (node (ref "C45") (pin "1") (pinfunction "1_1") (pintype "passive"))
      (node (ref "C46") (pin "1") (pinfunction "1_1") (pintype "passive"))
      (node (ref "C47") (pin "1") (pinfunction "1_1") (pintype "passive"))
      (node (ref "C48") (pin "1") (pinfunction "1_1") (pintype "passive"))
      (node (ref "C51") (pin "1") (pinfunction "1_1") (pintype "passive"))
      (node (ref "C53") (pin "1") (pinfunction "1_1") (pintype "passive"))
      (node (ref "J1") (pin "2") (pinfunction "2_2") (pintype "passive"))
      (node (ref "L10") (pin "1") (pinfunction "1_1") (pintype "bidirectional"))
      (node (ref "R12") (pin "1") (pinfunction "1_1") (pintype "passive"))
      (node (ref "S3") (pin "3") (pinfunction "3_3") (pintype "bidirectional"))
      (node (ref "U12") (pin "2") (pinfunction "VCC_2") (pintype "power_in"))
      (node (ref "U12") (pin "6") (pinfunction "PON_6") (pintype "input"))
      (node (ref "U13") (pin "2") (pinfunction "VCC_2") (pintype "power_in"))
      (node (ref "U13") (pin "6") (pinfunction "PON_6") (pintype "input"))
      (node (ref "U15") (pin "4") (pinfunction "VDD_4") (pintype "power_in"))
      (node (ref "U16") (pin "2") (pinfunction "VCC_2") (pintype "power_in"))
      (node (ref "U16") (pin "6") (pinfunction "PON_6") (pintype "input"))
      (node (ref "U18") (pin "2") (pinfunction "VCC_2") (pintype "power_in"))
      (node (ref "U18") (pin "6") (pinfunction "PON_6") (pintype "input"))
      (node (ref "U19") (pin "4") (pinfunction "VDD_4") (pintype "power_in"))
      (node (ref "U20") (pin "2") (pinfunction "~{SHDN}_2") (pintype "input"))
      (node (ref "U20") (pin "8") (pinfunction "VCC_8") (pintype "power_in"))
      (node (ref "U21") (pin "2") (pinfunction "~{SHDN}_2") (pintype "input"))
      (node (ref "U21") (pin "8") (pinfunction "VCC_8") (pintype "power_in"))
      (node (ref "U22") (pin "1") (pinfunction "OUT_1") (pintype "power_in"))
    )
    (net (code "2") (name "+3V0_DIGITAL") (class "Default")
      (node (ref "C1") (pin "1") (pinfunction "1_1") (pintype "passive"))
      (node (ref "C56") (pin "1") (pinfunction "1_1") (pintype "passive"))
      (node (ref "C58") (pin "1") (pinfunction "1_1") (pintype "passive"))
      (node (ref "C7") (pin "2") (pinfunction "2_2") (pintype "passive"))
      (node (ref "J1") (pin "3") (pinfunction "3_3") (pintype "passive"))
      (node (ref "J2") (pin "1") (pinfunction "VPP/MCLR_1") (pintype "passive"))
      (node (ref "J4") (pin "1") (pinfunction "VCC_1") (pintype "bidirectional"))
      (node (ref "L10") (pin "2") (pinfunction "2_2") (pintype "bidirectional"))
      (node (ref "U2") (pin "1") (pinfunction "VDD_1") (pintype "bidirectional"))
      (node (ref "U2") (pin "17") (pinfunction "VDD_17") (pintype "bidirectional"))
      (node (ref "U2") (pin "5") (pinfunction "VDDA_5") (pintype "bidirectional"))
    )
    (net (code "3") (name "+5V0") (class "Default")
      (node (ref "C15") (pin "2") (pinfunction "2_2") (pintype "passive"))
      (node (ref "C17") (pin "2") (pinfunction "2_2") (pintype "passive"))
      (node (ref "C23") (pin "1") (pinfunction "1_1") (pintype "passive"))
      (node (ref "C24") (pin "1") (pinfunction "1_1") (pintype "passive"))
      (node (ref "C28") (pin "2") (pinfunction "2_2") (pintype "passive"))
      (node (ref "C29") (pin "2") (pinfunction "2_2") (pintype "passive"))
      (node (ref "C38") (pin "1") (pinfunction "1_1") (pintype "passive"))
      (node (ref "C39") (pin "1") (pinfunction "1_1") (pintype "passive"))
      (node (ref "C49") (pin "1") (pinfunction "1_1") (pintype "passive"))
      (node (ref "C55") (pin "1") (pinfunction "1_1") (pintype "passive"))
      (node (ref "C57") (pin "1") (pinfunction "1_1") (pintype "passive"))
      (node (ref "C59") (pin "1") (pinfunction "1_1") (pintype "passive"))
      (node (ref "J1") (pin "1") (pinfunction "1_1") (pintype "passive"))
      (node (ref "L1") (pin "1") (pinfunction "1_1") (pintype "bidirectional"))
      (node (ref "L11") (pin "2") (pinfunction "2_2") (pintype "bidirectional"))
      (node (ref "L3") (pin "2") (pinfunction "2_2") (pintype "bidirectional"))
      (node (ref "L5") (pin "1") (pinfunction "1_1") (pintype "bidirectional"))
      (node (ref "L7") (pin "2") (pinfunction "2_2") (pintype "bidirectional"))
      (node (ref "LED1") (pin "A") (pinfunction "A_A") (pintype "passive"))
      (node (ref "LED2") (pin "A") (pinfunction "A_A") (pintype "passive"))
      (node (ref "LED3") (pin "A") (pinfunction "A_A") (pintype "passive"))
      (node (ref "LED4") (pin "A") (pinfunction "A_A") (pintype "passive"))
      (node (ref "LED5") (pin "A") (pinfunction "A_A") (pintype "passive"))
      (node (ref "LED6") (pin "A") (pinfunction "A_A") (pintype "passive"))
      (node (ref "LED7") (pin "A") (pinfunction "A_A") (pintype "passive"))
      (node (ref "LED8") (pin "A") (pinfunction "A_A") (pintype "passive"))
      (node (ref "U14") (pin "12") (pinfunction "VDD_12") (pintype "bidirectional"))
      (node (ref "U17") (pin "12") (pinfunction "VDD_12") (pintype "bidirectional"))
      (node (ref "U22") (pin "4") (pinfunction "EN_4") (pintype "input"))
      (node (ref "U22") (pin "6") (pinfunction "IN_6") (pintype "power_in"))
    )
    (net (code "4") (name "CELL_ANT") (class "Default")
      (node (ref "L13") (pin "2") (pinfunction "2_2") (pintype "bidirectional"))
      (node (ref "U7") (pin "6") (pinfunction "ANT_6") (pintype "bidirectional"))
      (node (ref "X2") (pin "ANTENNA") (pinfunction "ANT_ANTENNA") (pintype "bidirectional"))
    )
    (net (code "5") (name "GND") (class "Default")
      (node (ref "C1") (pin "2") (pinfunction "2_2") (pintype "passive"))
      (node (ref "C13") (pin "1") (pinfunction "1_1") (pintype "passive"))
      (node (ref "C14") (pin "1") (pinfunction "1_1") (pintype "passive"))
      (node (ref "C15") (pin "1") (pinfunction "1_1") (pintype "passive"))
      (node (ref "C16") (pin "1") (pinfunction "1_1") (pintype "passive"))
      (node (ref "C17") (pin "1") (pinfunction "1_1") (pintype "passive"))
      (node (ref "C18") (pin "1") (pinfunction "1_1") (pintype "passive"))
      (node (ref "C2") (pin "2") (pinfunction "2_2") (pintype "passive"))
      (node (ref "C22") (pin "2") (pinfunction "2_2") (pintype "passive"))
      (node (ref "C23") (pin "2") (pinfunction "2_2") (pintype "passive"))
      (node (ref "C24") (pin "2") (pinfunction "2_2") (pintype "passive"))
      (node (ref "C26") (pin "2") (pinfunction "2_2") (pintype "passive"))
      (node (ref "C27") (pin "1") (pinfunction "1_1") (pintype "passive"))
      (node (ref "C28") (pin "1") (pinfunction "1_1") (pintype "passive"))
      (node (ref "C29") (pin "1") (pinfunction "1_1") (pintype "passive"))
      (node (ref "C33") (pin "1") (pinfunction "1_1") (pintype "passive"))
      (node (ref "C34") (pin "1") (pinfunction "1_1") (pintype "passive"))
      (node (ref "C35") (pin "2") (pinfunction "2_2") (pintype "passive"))
      (node (ref "C36") (pin "1") (pinfunction "1_1") (pintype "passive"))
      (node (ref "C37") (pin "1") (pinfunction "1_1") (pintype "passive"))
      (node (ref "C38") (pin "2") (pinfunction "2_2") (pintype "passive"))
      (node (ref "C39") (pin "2") (pinfunction "2_2") (pintype "passive"))
      (node (ref "C41") (pin "2") (pinfunction "2_2") (pintype "passive"))
      (node (ref "C42") (pin "1") (pinfunction "1_1") (pintype "passive"))
      (node (ref "C43") (pin "2") (pinfunction "2_2") (pintype "passive"))
      (node (ref "C44") (pin "2") (pinfunction "2_2") (pintype "passive"))
      (node (ref "C45") (pin "2") (pinfunction "2_2") (pintype "passive"))
      (node (ref "C46") (pin "2") (pinfunction "2_2") (pintype "passive"))
      (node (ref "C47") (pin "2") (pinfunction "2_2") (pintype "passive"))
      (node (ref "C48") (pin "2") (pinfunction "2_2") (pintype "passive"))
      (node (ref "C49") (pin "2") (pinfunction "2_2") (pintype "passive"))
      (node (ref "C50") (pin "2") (pinfunction "2_2") (pintype "passive"))
      (node (ref "C51") (pin "2") (pinfunction "2_2") (pintype "passive"))
      (node (ref "C52") (pin "2") (pinfunction "2_2") (pintype "passive"))
      (node (ref "C53") (pin "2") (pinfunction "2_2") (pintype "passive"))
      (node (ref "C54") (pin "2") (pinfunction "2_2") (pintype "passive"))
      (node (ref "C55") (pin "2") (pinfunction "2_2") (pintype "passive"))
      (node (ref "C56") (pin "2") (pinfunction "2_2") (pintype "passive"))
      (node (ref "C57") (pin "2") (pinfunction "2_2") (pintype "passive"))
      (node (ref "C58") (pin "2") (pinfunction "2_2") (pintype "passive"))
      (node (ref "C59") (pin "2") (pinfunction "2_2") (pintype "passive"))
      (node (ref "C7") (pin "1") (pinfunction "1_1") (pintype "passive"))
      (node (ref "HY1") (pin "P$2") (pinfunction "GND_P$2") (pintype "bidirectional"))
      (node (ref "HY1") (pin "P$5") (pinfunction "GND_P$5") (pintype "bidirectional"))
      (node (ref "HY2") (pin "P$2") (pinfunction "GND_P$2") (pintype "bidirectional"))
      (node (ref "HY2") (pin "P$5") (pinfunction "GND_P$5") (pintype "bidirectional"))
      (node (ref "IC1") (pin "4") (pinfunction "PGND_4") (pintype "power_in"))
      (node (ref "IC1") (pin "9") (pinfunction "GND_9") (pintype "power_in"))
      (node (ref "IC1") (pin "PP") (pinfunction "PP_PP") (pintype "power_in"))
      (node (ref "IC1") (pin "PP@1") (pinfunction "PP_PP@1") (pintype "power_in"))
      (node (ref "IC1") (pin "PP@2") (pinfunction "PP_PP@2") (pintype "power_in"))
      (node (ref "J1") (pin "10") (pinfunction "10_10") (pintype "passive"))
      (node (ref "J1") (pin "4") (pinfunction "4_4") (pintype "passive"))
      (node (ref "J1") (pin "7") (pinfunction "7_7") (pintype "passive"))
      (node (ref "J2") (pin "5") (pinfunction "ICSP_CLK/PGC_5") (pintype "output"))
      (node (ref "J3") (pin "2") (pinfunction "2_2") (pintype "bidirectional"))
      (node (ref "J4") (pin "5") (pinfunction "GND_5") (pintype "bidirectional"))
      (node (ref "L12") (pin "1") (pinfunction "1_1") (pintype "bidirectional"))
      (node (ref "L13") (pin "1") (pinfunction "1_1") (pintype "bidirectional"))
      (node (ref "Q1") (pin "2") (pinfunction "S_2") (pintype "bidirectional"))
      (node (ref "R10") (pin "2") (pinfunction "2_2") (pintype "passive"))
      (node (ref "R11") (pin "2") (pinfunction "2_2") (pintype "passive"))
      (node (ref "R13") (pin "2") (pinfunction "2_2") (pintype "passive"))
      (node (ref "R2") (pin "1") (pinfunction "1_1") (pintype "passive"))
      (node (ref "R8") (pin "2") (pinfunction "2_2") (pintype "passive"))
      (node (ref "R9") (pin "2") (pinfunction "2_2") (pintype "passive"))
      (node (ref "S1") (pin "P$3") (pinfunction "P$3_P$3") (pintype "bidirectional"))
      (node (ref "S5") (pin "P$3") (pinfunction "P$3_P$3") (pintype "bidirectional"))
      (node (ref "U12") (pin "1") (pinfunction "GND_1") (pintype "power_in"))
      (node (ref "U12") (pin "4") (pinfunction "GND_4") (pintype "power_in"))
      (node (ref "U13") (pin "1") (pinfunction "GND_1") (pintype "power_in"))
      (node (ref "U13") (pin "4") (pinfunction "GND_4") (pintype "power_in"))
      (node (ref "U14") (pin "1") (pinfunction "GND_1") (pintype "bidirectional"))
      (node (ref "U14") (pin "11") (pinfunction "GND_11") (pintype "bidirectional"))
      (node (ref "U14") (pin "17") (pinfunction "GND_17") (pintype "bidirectional"))
      (node (ref "U14") (pin "18") (pinfunction "GND_18") (pintype "bidirectional"))
      (node (ref "U14") (pin "19") (pinfunction "GND_19") (pintype "bidirectional"))
      (node (ref "U14") (pin "2") (pinfunction "GND_2") (pintype "bidirectional"))
      (node (ref "U14") (pin "21") (pinfunction "GND_21") (pintype "bidirectional"))
      (node (ref "U14") (pin "22") (pinfunction "GND_22") (pintype "bidirectional"))
      (node (ref "U14") (pin "24") (pinfunction "GND_24") (pintype "bidirectional"))
      (node (ref "U14") (pin "25") (pinfunction "GND_25") (pintype "bidirectional"))
      (node (ref "U14") (pin "4") (pinfunction "GND_4") (pintype "bidirectional"))
      (node (ref "U14") (pin "6") (pinfunction "GND_6") (pintype "bidirectional"))
      (node (ref "U14") (pin "7") (pinfunction "GND_7") (pintype "bidirectional"))
      (node (ref "U14") (pin "9") (pinfunction "GND_9") (pintype "bidirectional"))
      (node (ref "U15") (pin "2") (pinfunction "GND_2") (pintype "power_in"))
      (node (ref "U16") (pin "1") (pinfunction "GND_1") (pintype "power_in"))
      (node (ref "U16") (pin "4") (pinfunction "GND_4") (pintype "power_in"))
      (node (ref "U17") (pin "1") (pinfunction "GND_1") (pintype "bidirectional"))
      (node (ref "U17") (pin "11") (pinfunction "GND_11") (pintype "bidirectional"))
      (node (ref "U17") (pin "17") (pinfunction "GND_17") (pintype "bidirectional"))
      (node (ref "U17") (pin "18") (pinfunction "GND_18") (pintype "bidirectional"))
      (node (ref "U17") (pin "19") (pinfunction "GND_19") (pintype "bidirectional"))
      (node (ref "U17") (pin "2") (pinfunction "GND_2") (pintype "bidirectional"))
      (node (ref "U17") (pin "21") (pinfunction "GND_21") (pintype "bidirectional"))
      (node (ref "U17") (pin "22") (pinfunction "GND_22") (pintype "bidirectional"))
      (node (ref "U17") (pin "24") (pinfunction "GND_24") (pintype "bidirectional"))
      (node (ref "U17") (pin "25") (pinfunction "GND_25") (pintype "bidirectional"))
      (node (ref "U17") (pin "4") (pinfunction "GND_4") (pintype "bidirectional"))
      (node (ref "U17") (pin "6") (pinfunction "GND_6") (pintype "bidirectional"))
      (node (ref "U17") (pin "7") (pinfunction "GND_7") (pintype "bidirectional"))
      (node (ref "U17") (pin "9") (pinfunction "GND_9") (pintype "bidirectional"))
      (node (ref "U18") (pin "1") (pinfunction "GND_1") (pintype "power_in"))
      (node (ref "U18") (pin "4") (pinfunction "GND_4") (pintype "power_in"))
      (node (ref "U19") (pin "2") (pinfunction "GND_2") (pintype "power_in"))
      (node (ref "U2") (pin "16") (pinfunction "VSS_16") (pintype "bidirectional"))
      (node (ref "U2") (pin "32") (pinfunction "VSS_32") (pintype "bidirectional"))
      (node (ref "U20") (pin "3") (pinfunction "GND_2_3") (pintype "power_in"))
      (node (ref "U20") (pin "5") (pinfunction "GND_5") (pintype "power_in"))
      (node (ref "U21") (pin "3") (pinfunction "GND_2_3") (pintype "power_in"))
      (node (ref "U21") (pin "5") (pinfunction "GND_5") (pintype "power_in"))
      (node (ref "U22") (pin "5") (pinfunction "GND_5") (pintype "power_in"))
      (node (ref "U22") (pin "7") (pinfunction "PAD_7") (pintype "power_in"))
      (node (ref "U5") (pin "2") (pinfunction "GND_2") (pintype "bidirectional"))
      (node (ref "U5") (pin "4") (pinfunction "GND_4") (pintype "bidirectional"))
      (node (ref "U5") (pin "5") (pinfunction "GND_5") (pintype "bidirectional"))
      (node (ref "U5") (pin "7") (pinfunction "GND_7") (pintype "bidirectional"))
      (node (ref "U5") (pin "8") (pinfunction "GND_8") (pintype "bidirectional"))
      (node (ref "U7") (pin "2") (pinfunction "GND_2") (pintype "bidirectional"))
      (node (ref "U7") (pin "4") (pinfunction "GND_4") (pintype "bidirectional"))
      (node (ref "U7") (pin "5") (pinfunction "GND_5") (pintype "bidirectional"))
      (node (ref "U7") (pin "7") (pinfunction "GND_7") (pintype "bidirectional"))
      (node (ref "U7") (pin "8") (pinfunction "GND_8") (pintype "bidirectional"))
      (node (ref "X1") (pin "GND1") (pinfunction "GND1_GND1") (pintype "power_in"))
      (node (ref "X1") (pin "GND2") (pinfunction "GND2_GND2") (pintype "power_in"))
      (node (ref "X1") (pin "GND3") (pinfunction "GND3_GND3") (pintype "power_in"))
      (node (ref "X1") (pin "GND4") (pinfunction "GND4_GND4") (pintype "power_in"))
      (node (ref "X2") (pin "GND1") (pinfunction "GND1_GND1") (pintype "power_in"))
      (node (ref "X2") (pin "GND2") (pinfunction "GND2_GND2") (pintype "power_in"))
      (node (ref "X2") (pin "GND3") (pinfunction "GND3_GND3") (pintype "power_in"))
      (node (ref "X2") (pin "GND4") (pinfunction "GND4_GND4") (pintype "power_in"))
    )
    (net (code "6") (name "Net-(C25-Pad1)") (class "Default")
      (node (ref "C25") (pin "1") (pinfunction "1_1") (pintype "passive"))
      (node (ref "L4") (pin "2") (pinfunction "2_2") (pintype "bidirectional"))
    )
    (net (code "7") (name "Net-(C40-Pad1)") (class "Default")
      (node (ref "C40") (pin "1") (pinfunction "1_1") (pintype "passive"))
      (node (ref "L8") (pin "2") (pinfunction "2_2") (pintype "bidirectional"))
    )
    (net (code "8") (name "Net-(HY1-50)") (class "Default")
      (node (ref "HY1") (pin "P$4") (pinfunction "50_P$4") (pintype "bidirectional"))
      (node (ref "R8") (pin "1") (pinfunction "1_1") (pintype "passive"))
    )
    (net (code "9") (name "Net-(HY1-COUPLE)") (class "Default")
      (node (ref "HY1") (pin "P$6") (pinfunction "COUPLE_P$6") (pintype "bidirectional"))
      (node (ref "R10") (pin "1") (pinfunction "1_1") (pintype "passive"))
      (node (ref "U21") (pin "1") (pinfunction "RFIN_1") (pintype "input"))
    )
    (net (code "10") (name "Net-(HY2-50)") (class "Default")
      (node (ref "HY2") (pin "P$4") (pinfunction "50_P$4") (pintype "bidirectional"))
      (node (ref "R9") (pin "1") (pinfunction "1_1") (pintype "passive"))
    )
    (net (code "11") (name "Net-(HY2-COUPLE)") (class "Default")
      (node (ref "HY2") (pin "P$6") (pinfunction "COUPLE_P$6") (pintype "bidirectional"))
      (node (ref "R11") (pin "1") (pinfunction "1_1") (pintype "passive"))
      (node (ref "U20") (pin "1") (pinfunction "RFIN_1") (pintype "input"))
    )
    (net (code "12") (name "Net-(IC1-FB)") (class "Default")
      (node (ref "C54") (pin "1") (pinfunction "1_1") (pintype "passive"))
      (node (ref "IC1") (pin "10") (pinfunction "FB_10") (pintype "input"))
      (node (ref "IC1") (pin "2") (pinfunction "VOUT_2") (pintype "passive"))
      (node (ref "L11") (pin "1") (pinfunction "1_1") (pintype "bidirectional"))
    )
    (net (code "13") (name "Net-(IC1-L)") (class "Default")
      (node (ref "IC1") (pin "3") (pinfunction "L_3") (pintype "input"))
      (node (ref "L9") (pin "1") (pinfunction "1_1") (pintype "passive"))
    )
    (net (code "14") (name "Net-(IC1-VAUX)") (class "Default")
      (node (ref "C52") (pin "1") (pinfunction "1_1") (pintype "passive"))
      (node (ref "IC1") (pin "1") (pinfunction "VAUX_1") (pintype "bidirectional"))
    )
    (net (code "15") (name "Net-(J3-Pad1)") (class "Default")
      (node (ref "J3") (pin "1") (pinfunction "1_1") (pintype "bidirectional"))
      (node (ref "S4") (pin "3") (pinfunction "3_3") (pintype "bidirectional"))
    )
    (net (code "16") (name "Net-(L2-Pad1)") (class "Default")
      (node (ref "L2") (pin "1") (pinfunction "1_1") (pintype "bidirectional"))
      (node (ref "R6") (pin "1") (pinfunction "1_1") (pintype "passive"))
    )
    (net (code "17") (name "Net-(L6-Pad1)") (class "Default")
      (node (ref "L6") (pin "1") (pinfunction "1_1") (pintype "bidirectional"))
      (node (ref "R7") (pin "1") (pinfunction "1_1") (pintype "passive"))
    )
    (net (code "18") (name "Net-(LED1-PadC)") (class "Default")
      (node (ref "LED1") (pin "C") (pinfunction "C_C") (pintype "passive"))
      (node (ref "R3") (pin "2") (pinfunction "2_2") (pintype "passive"))
    )
    (net (code "19") (name "Net-(LED2-PadC)") (class "Default")
      (node (ref "LED2") (pin "C") (pinfunction "C_C") (pintype "passive"))
      (node (ref "R4") (pin "2") (pinfunction "2_2") (pintype "passive"))
    )
    (net (code "20") (name "Net-(LED3-PadC)") (class "Default")
      (node (ref "LED3") (pin "C") (pinfunction "C_C") (pintype "passive"))
      (node (ref "R5") (pin "2") (pinfunction "2_2") (pintype "passive"))
    )
    (net (code "21") (name "Net-(LED4-PadC)") (class "Default")
      (node (ref "LED4") (pin "C") (pinfunction "C_C") (pintype "passive"))
      (node (ref "R14") (pin "2") (pinfunction "2_2") (pintype "passive"))
    )
    (net (code "22") (name "Net-(LED5-PadC)") (class "Default")
      (node (ref "LED5") (pin "C") (pinfunction "C_C") (pintype "passive"))
      (node (ref "R15") (pin "2") (pinfunction "2_2") (pintype "passive"))
    )
    (net (code "23") (name "Net-(LED6-PadC)") (class "Default")
      (node (ref "LED6") (pin "C") (pinfunction "C_C") (pintype "passive"))
      (node (ref "R16") (pin "2") (pinfunction "2_2") (pintype "passive"))
    )
    (net (code "24") (name "Net-(LED7-PadC)") (class "Default")
      (node (ref "LED7") (pin "C") (pinfunction "C_C") (pintype "passive"))
      (node (ref "R17") (pin "2") (pinfunction "2_2") (pintype "passive"))
    )
    (net (code "25") (name "Net-(LED8-PadC)") (class "Default")
      (node (ref "LED8") (pin "C") (pinfunction "C_C") (pintype "passive"))
      (node (ref "R18") (pin "2") (pinfunction "2_2") (pintype "passive"))
    )
    (net (code "26") (name "Net-(Q1-D)") (class "Default")
      (node (ref "Q1") (pin "3") (pinfunction "D_3") (pintype "bidirectional"))
      (node (ref "R12") (pin "2") (pinfunction "2_2") (pintype "passive"))
      (node (ref "U15") (pin "6") (pinfunction "CTRL_6") (pintype "input"))
    )
    (net (code "27") (name "Net-(R19-Pad2)") (class "Default")
      (node (ref "R19") (pin "2") (pinfunction "2_2") (pintype "passive"))
      (node (ref "S5") (pin "P$1") (pinfunction "P$1_P$1") (pintype "bidirectional"))
    )
    (net (code "28") (name "Net-(U2-BOOT0)") (class "Default")
      (node (ref "R13") (pin "1") (pinfunction "1_1") (pintype "passive"))
      (node (ref "U2") (pin "31") (pinfunction "BOOT0_31") (pintype "bidirectional"))
    )
    (net (code "29") (name "Net-(U2-PA0)") (class "Default")
      (node (ref "C2") (pin "1") (pinfunction "1_1") (pintype "passive"))
      (node (ref "R19") (pin "1") (pinfunction "1_1") (pintype "passive"))
      (node (ref "U2") (pin "6") (pinfunction "PA0_6") (pintype "bidirectional"))
    )
    (net (code "30") (name "Net-(U2-PA8)") (class "Default")
      (node (ref "R14") (pin "1") (pinfunction "1_1") (pintype "passive"))
      (node (ref "U2") (pin "18") (pinfunction "PA8_18") (pintype "bidirectional"))
    )
    (net (code "31") (name "Net-(U2-PA9)") (class "Default")
      (node (ref "R5") (pin "1") (pinfunction "1_1") (pintype "passive"))
      (node (ref "U2") (pin "19") (pinfunction "PA9_19") (pintype "bidirectional"))
    )
    (net (code "32") (name "Net-(U2-PA10)") (class "Default")
      (node (ref "R4") (pin "1") (pinfunction "1_1") (pintype "passive"))
      (node (ref "U2") (pin "20") (pinfunction "PA10_20") (pintype "bidirectional"))
    )
    (net (code "33") (name "Net-(U2-PA15)") (class "Default")
      (node (ref "R3") (pin "1") (pinfunction "1_1") (pintype "passive"))
      (node (ref "U2") (pin "25") (pinfunction "PA15_25") (pintype "bidirectional"))
    )
    (net (code "34") (name "Net-(U2-PB3)") (class "Default")
      (node (ref "R18") (pin "1") (pinfunction "1_1") (pintype "passive"))
      (node (ref "U2") (pin "26") (pinfunction "PB3_26") (pintype "bidirectional"))
    )
    (net (code "35") (name "Net-(U2-PB4)") (class "Default")
      (node (ref "R17") (pin "1") (pinfunction "1_1") (pintype "passive"))
      (node (ref "U2") (pin "27") (pinfunction "PB4_27") (pintype "bidirectional"))
    )
    (net (code "36") (name "Net-(U2-PB5)") (class "Default")
      (node (ref "R16") (pin "1") (pinfunction "1_1") (pintype "passive"))
      (node (ref "U2") (pin "28") (pinfunction "PB5_28") (pintype "bidirectional"))
    )
    (net (code "37") (name "Net-(U2-PB6)") (class "Default")
      (node (ref "R15") (pin "1") (pinfunction "1_1") (pintype "passive"))
      (node (ref "U2") (pin "29") (pinfunction "PB6_29") (pintype "bidirectional"))
    )
    (net (code "38") (name "Net-(U12-AO)") (class "Default")
      (node (ref "U12") (pin "3") (pinfunction "AO_3") (pintype "output"))
      (node (ref "U13") (pin "5") (pinfunction "AI_5") (pintype "input"))
    )
    (net (code "39") (name "Net-(U13-AO)") (class "Default")
      (node (ref "C21") (pin "1") (pinfunction "1_1") (pintype "passive"))
      (node (ref "U13") (pin "3") (pinfunction "AO_3") (pintype "output"))
    )
    (net (code "40") (name "Net-(U14-AMP1_IN)") (class "Default")
      (node (ref "C21") (pin "2") (pinfunction "2_2") (pintype "passive"))
      (node (ref "U14") (pin "8") (pinfunction "AMP1_IN_8") (pintype "bidirectional"))
    )
    (net (code "41") (name "Net-(U14-AMP1_OUT{slash}VCC)") (class "Default")
      (node (ref "C19") (pin "1") (pinfunction "1_1") (pintype "passive"))
      (node (ref "L1") (pin "2") (pinfunction "2_2") (pintype "bidirectional"))
      (node (ref "U14") (pin "5") (pinfunction "AMP1_OUT/VCC_5") (pintype "bidirectional"))
    )
    (net (code "42") (name "Net-(U14-AMP2_IN)") (class "Default")
      (node (ref "R6") (pin "2") (pinfunction "2_2") (pintype "passive"))
      (node (ref "U14") (pin "20") (pinfunction "AMP2_IN_20") (pintype "bidirectional"))
    )
    (net (code "43") (name "Net-(U14-AMP2_OUT{slash}VCC)") (class "Default")
      (node (ref "L3") (pin "1") (pinfunction "1_1") (pintype "bidirectional"))
      (node (ref "L4") (pin "1") (pinfunction "1_1") (pintype "bidirectional"))
      (node (ref "U14") (pin "16") (pinfunction "AMP2_OUT/VCC_16") (pintype "bidirectional"))
    )
    (net (code "44") (name "Net-(U14-DSA_IN)") (class "Default")
      (node (ref "C19") (pin "2") (pinfunction "2_2") (pintype "passive"))
      (node (ref "U14") (pin "3") (pinfunction "DSA_IN_3") (pintype "bidirectional"))
    )
    (net (code "45") (name "Net-(U14-DSA_OUT)") (class "Default")
      (node (ref "C20") (pin "2") (pinfunction "2_2") (pintype "passive"))
      (node (ref "U14") (pin "23") (pinfunction "DSA_OUT_23") (pintype "bidirectional"))
    )
    (net (code "46") (name "Net-(U15-RF1)") (class "Default")
      (node (ref "U15") (pin "3") (pinfunction "RF1_3") (pintype "bidirectional"))
      (node (ref "U19") (pin "1") (pinfunction "RF2_1") (pintype "bidirectional"))
    )
    (net (code "47") (name "Net-(U15-RF2)") (class "Default")
      (node (ref "U15") (pin "1") (pinfunction "RF2_1") (pintype "bidirectional"))
      (node (ref "U16") (pin "3") (pinfunction "AO_3") (pintype "output"))
    )
    (net (code "48") (name "Net-(U15-RFIN)") (class "Default")
      (node (ref "C32") (pin "1") (pinfunction "1_1") (pintype "passive"))
      (node (ref "U15") (pin "5") (pinfunction "RFIN_5") (pintype "bidirectional"))
    )
    (net (code "49") (name "Net-(U16-AI)") (class "Default")
      (node (ref "U16") (pin "5") (pinfunction "AI_5") (pintype "input"))
      (node (ref "U18") (pin "3") (pinfunction "AO_3") (pintype "output"))
    )
    (net (code "50") (name "Net-(U17-AMP1_IN)") (class "Default")
      (node (ref "C32") (pin "2") (pinfunction "2_2") (pintype "passive"))
      (node (ref "U17") (pin "8") (pinfunction "AMP1_IN_8") (pintype "bidirectional"))
    )
    (net (code "51") (name "Net-(U17-AMP1_OUT{slash}VCC)") (class "Default")
      (node (ref "C30") (pin "1") (pinfunction "1_1") (pintype "passive"))
      (node (ref "L5") (pin "2") (pinfunction "2_2") (pintype "bidirectional"))
      (node (ref "U17") (pin "5") (pinfunction "AMP1_OUT/VCC_5") (pintype "bidirectional"))
    )
    (net (code "52") (name "Net-(U17-AMP2_IN)") (class "Default")
      (node (ref "R7") (pin "2") (pinfunction "2_2") (pintype "passive"))
      (node (ref "U17") (pin "20") (pinfunction "AMP2_IN_20") (pintype "bidirectional"))
    )
    (net (code "53") (name "Net-(U17-AMP2_OUT{slash}VCC)") (class "Default")
      (node (ref "L7") (pin "1") (pinfunction "1_1") (pintype "bidirectional"))
      (node (ref "L8") (pin "1") (pinfunction "1_1") (pintype "bidirectional"))
      (node (ref "U17") (pin "16") (pinfunction "AMP2_OUT/VCC_16") (pintype "bidirectional"))
    )
    (net (code "54") (name "Net-(U17-DSA_IN)") (class "Default")
      (node (ref "C30") (pin "2") (pinfunction "2_2") (pintype "passive"))
      (node (ref "U17") (pin "3") (pinfunction "DSA_IN_3") (pintype "bidirectional"))
    )
    (net (code "55") (name "Net-(U17-DSA_OUT)") (class "Default")
      (node (ref "C31") (pin "2") (pinfunction "2_2") (pintype "passive"))
      (node (ref "U17") (pin "23") (pinfunction "DSA_OUT_23") (pintype "bidirectional"))
    )
    (net (code "56") (name "Net-(U18-AI)") (class "Default")
      (node (ref "U18") (pin "5") (pinfunction "AI_5") (pintype "input"))
      (node (ref "U19") (pin "3") (pinfunction "RF1_3") (pintype "bidirectional"))
    )
    (net (code "57") (name "Net-(U20-CLPF)") (class "Default")
      (node (ref "C43") (pin "1") (pinfunction "1_1") (pintype "passive"))
      (node (ref "U20") (pin "4") (pinfunction "CLPF_4") (pintype "passive"))
    )
    (net (code "58") (name "Net-(U21-CLPF)") (class "Default")
      (node (ref "C44") (pin "1") (pinfunction "1_1") (pintype "passive"))
      (node (ref "U21") (pin "4") (pinfunction "CLPF_4") (pintype "passive"))
    )
    (net (code "59") (name "POWER+") (class "Default")
      (node (ref "C50") (pin "1") (pinfunction "1_1") (pintype "passive"))
      (node (ref "IC1") (pin "5") (pinfunction "VIN_5") (pintype "input"))
      (node (ref "IC1") (pin "6") (pinfunction "EN_6") (pintype "input"))
      (node (ref "IC1") (pin "7") (pinfunction "UVLO_7") (pintype "input"))
      (node (ref "IC1") (pin "8") (pinfunction "PS_8") (pintype "input"))
      (node (ref "L9") (pin "2") (pinfunction "2_2") (pintype "passive"))
      (node (ref "S4") (pin "2") (pinfunction "2_2") (pintype "bidirectional"))
    )
    (net (code "60") (name "PWR_ADC1") (class "Default")
      (node (ref "J1") (pin "5") (pinfunction "5_5") (pintype "passive"))
      (node (ref "U2") (pin "15") (pinfunction "PB1_15") (pintype "bidirectional"))
      (node (ref "U20") (pin "7") (pinfunction "OUT_7") (pintype "output"))
    )
    (net (code "61") (name "PWR_ADC2") (class "Default")
      (node (ref "J1") (pin "6") (pinfunction "6_6") (pintype "passive"))
      (node (ref "U2") (pin "14") (pinfunction "PB0_14") (pintype "bidirectional"))
      (node (ref "U21") (pin "7") (pinfunction "OUT_7") (pintype "output"))
    )
    (net (code "62") (name "RESET") (class "Default")
      (node (ref "J2") (pin "3") (pinfunction "VSS(GND)_3") (pintype "power_in"))
      (node (ref "S1") (pin "P$1") (pinfunction "P$1_P$1") (pintype "bidirectional"))
      (node (ref "U2") (pin "4") (pinfunction "NRST_4") (pintype "bidirectional"))
    )
    (net (code "63") (name "RX_DIRECTIONAL_COUPLER") (class "Default")
      (node (ref "C25") (pin "2") (pinfunction "2_2") (pintype "passive"))
      (node (ref "C26") (pin "1") (pinfunction "1_1") (pintype "passive"))
      (node (ref "HY1") (pin "P$1") (pinfunction "IN_P$1") (pintype "bidirectional"))
    )
    (net (code "64") (name "RX_DSA_OUT") (class "Default")
      (node (ref "C20") (pin "1") (pinfunction "1_1") (pintype "passive"))
      (node (ref "C22") (pin "1") (pinfunction "1_1") (pintype "passive"))
      (node (ref "L2") (pin "2") (pinfunction "2_2") (pintype "bidirectional"))
    )
    (net (code "65") (name "RX_PATH_CELL") (class "Default")
      (node (ref "HY1") (pin "P$3") (pinfunction "OUT_P$3") (pintype "bidirectional"))
      (node (ref "U7") (pin "1") (pinfunction "RX_1") (pintype "bidirectional"))
    )
    (net (code "66") (name "RX_PATH_TOWER") (class "Default")
      (node (ref "U12") (pin "5") (pinfunction "AI_5") (pintype "input"))
      (node (ref "U5") (pin "1") (pinfunction "RX_1") (pintype "bidirectional"))
    )
    (net (code "67") (name "SPI1_CS1") (class "Default")
      (node (ref "U14") (pin "15") (pinfunction "LE_15") (pintype "bidirectional"))
      (node (ref "U2") (pin "10") (pinfunction "PA4_10") (pintype "bidirectional"))
    )
    (net (code "68") (name "SPI1_CS2") (class "Default")
      (node (ref "U17") (pin "15") (pinfunction "LE_15") (pintype "bidirectional"))
      (node (ref "U2") (pin "9") (pinfunction "PA3_9") (pintype "bidirectional"))
    )
    (net (code "69") (name "SPI1_MISO") (class "Default")
      (node (ref "U14") (pin "10") (pinfunction "SOD_10") (pintype "bidirectional"))
      (node (ref "U17") (pin "10") (pinfunction "SOD_10") (pintype "bidirectional"))
      (node (ref "U2") (pin "12") (pinfunction "PA6_12") (pintype "bidirectional"))
    )
    (net (code "70") (name "SPI1_MOSI") (class "Default")
      (node (ref "U14") (pin "14") (pinfunction "DATA_14") (pintype "bidirectional"))
      (node (ref "U17") (pin "14") (pinfunction "DATA_14") (pintype "bidirectional"))
      (node (ref "U2") (pin "13") (pinfunction "PA7_13") (pintype "bidirectional"))
    )
    (net (code "71") (name "SPI1_SCK") (class "Default")
      (node (ref "U14") (pin "13") (pinfunction "CLK_13") (pintype "bidirectional"))
      (node (ref "U17") (pin "13") (pinfunction "CLK_13") (pintype "bidirectional"))
      (node (ref "U2") (pin "11") (pinfunction "PA5_11") (pintype "bidirectional"))
    )
    (net (code "72") (name "SWCLK") (class "Default")
      (node (ref "J2") (pin "4") (pinfunction "ICSP_DAT/PGD_4") (pintype "bidirectional"))
      (node (ref "U2") (pin "24") (pinfunction "PA14_24") (pintype "bidirectional"))
    )
    (net (code "73") (name "SWDIO") (class "Default")
      (node (ref "J2") (pin "2") (pinfunction "VDD_2") (pintype "power_in"))
      (node (ref "U2") (pin "23") (pinfunction "PA13_23") (pintype "bidirectional"))
    )
    (net (code "74") (name "TOWER_ANT") (class "Default")
      (node (ref "L12") (pin "2") (pinfunction "2_2") (pintype "bidirectional"))
      (node (ref "U5") (pin "6") (pinfunction "ANT_6") (pintype "bidirectional"))
      (node (ref "X1") (pin "ANTENNA") (pinfunction "ANT_ANTENNA") (pintype "bidirectional"))
    )
    (net (code "75") (name "TX_DIRECTIONAL_COUPLER") (class "Default")
      (node (ref "C40") (pin "2") (pinfunction "2_2") (pintype "passive"))
      (node (ref "C41") (pin "1") (pinfunction "1_1") (pintype "passive"))
      (node (ref "HY2") (pin "P$1") (pinfunction "IN_P$1") (pintype "bidirectional"))
    )
    (net (code "76") (name "TX_DSA_OUT") (class "Default")
      (node (ref "C31") (pin "1") (pinfunction "1_1") (pintype "passive"))
      (node (ref "C35") (pin "1") (pinfunction "1_1") (pintype "passive"))
      (node (ref "L6") (pin "2") (pinfunction "2_2") (pintype "bidirectional"))
    )
    (net (code "77") (name "TX_LNA_BYPASS") (class "Default")
      (node (ref "J1") (pin "8") (pinfunction "8_8") (pintype "passive"))
      (node (ref "Q1") (pin "1") (pinfunction "G_1") (pintype "bidirectional"))
      (node (ref "R2") (pin "2") (pinfunction "2_2") (pintype "passive"))
      (node (ref "S3") (pin "2") (pinfunction "2_2") (pintype "bidirectional"))
      (node (ref "U19") (pin "6") (pinfunction "CTRL_6") (pintype "input"))
      (node (ref "U2") (pin "7") (pinfunction "PA1_7") (pintype "bidirectional"))
    )
    (net (code "78") (name "TX_PATH_CELL") (class "Default")
      (node (ref "U19") (pin "5") (pinfunction "RFIN_5") (pintype "bidirectional"))
      (node (ref "U7") (pin "3") (pinfunction "TX_3") (pintype "bidirectional"))
    )
    (net (code "79") (name "TX_PATH_TOWER") (class "Default")
      (node (ref "HY2") (pin "P$3") (pinfunction "OUT_P$3") (pintype "bidirectional"))
      (node (ref "U5") (pin "3") (pinfunction "TX_3") (pintype "bidirectional"))
    )
    (net (code "80") (name "USB_D_N") (class "Default")
      (node (ref "J4") (pin "2") (pinfunction "D-_2") (pintype "bidirectional"))
      (node (ref "U2") (pin "21") (pinfunction "PA11_21") (pintype "bidirectional"))
    )
    (net (code "81") (name "USB_D_P") (class "Default")
      (node (ref "J4") (pin "3") (pinfunction "D+_3") (pintype "bidirectional"))
      (node (ref "U2") (pin "22") (pinfunction "PA12_22") (pintype "bidirectional"))
    )
    (net (code "82") (name "unconnected-(J1-Pad9)") (class "Default")
      (node (ref "J1") (pin "9") (pinfunction "9_9") (pintype "passive"))
    )
    (net (code "83") (name "unconnected-(J2-LVP-Pad6)") (class "Default")
      (node (ref "J2") (pin "6") (pinfunction "LVP_6") (pintype "bidirectional"))
    )
    (net (code "84") (name "unconnected-(J4-ID-Pad4)") (class "Default")
      (node (ref "J4") (pin "4") (pinfunction "ID_4") (pintype "bidirectional"))
    )
    (net (code "85") (name "unconnected-(S1-PadP$2)") (class "Default")
      (node (ref "S1") (pin "P$2") (pinfunction "P$2_P$2") (pintype "bidirectional"))
    )
    (net (code "86") (name "unconnected-(S1-PadP$4)") (class "Default")
      (node (ref "S1") (pin "P$4") (pinfunction "P$4_P$4") (pintype "bidirectional"))
    )
    (net (code "87") (name "unconnected-(S3-Pad1)") (class "Default")
      (node (ref "S3") (pin "1") (pinfunction "1_1") (pintype "bidirectional"))
    )
    (net (code "88") (name "unconnected-(S4-Pad1)") (class "Default")
      (node (ref "S4") (pin "1") (pinfunction "1_1") (pintype "bidirectional"))
    )
    (net (code "89") (name "unconnected-(S5-PadP$2)") (class "Default")
      (node (ref "S5") (pin "P$2") (pinfunction "P$2_P$2") (pintype "bidirectional"))
    )
    (net (code "90") (name "unconnected-(S5-PadP$4)") (class "Default")
      (node (ref "S5") (pin "P$4") (pinfunction "P$4_P$4") (pintype "bidirectional"))
    )
    (net (code "91") (name "unconnected-(U2-PA2-Pad8)") (class "Default")
      (node (ref "U2") (pin "8") (pinfunction "PA2_8") (pintype "bidirectional"))
    )
    (net (code "92") (name "unconnected-(U2-PB7-Pad30)") (class "Default")
      (node (ref "U2") (pin "30") (pinfunction "PB7_30") (pintype "bidirectional"))
    )
    (net (code "93") (name "unconnected-(U2-PC14-OSC32_IN-Pad2)") (class "Default")
      (node (ref "U2") (pin "2") (pinfunction "PC14-OSC32_IN_2") (pintype "bidirectional"))
    )
    (net (code "94") (name "unconnected-(U2-PC15-OSC32_OUT-Pad3)") (class "Default")
      (node (ref "U2") (pin "3") (pinfunction "PC15-OSC32_OUT_3") (pintype "bidirectional"))
    )
    (net (code "95") (name "unconnected-(U20-NC-Pad6)") (class "Default")
      (node (ref "U20") (pin "6") (pinfunction "NC_6") (pintype "no_connect"))
    )
    (net (code "96") (name "unconnected-(U21-NC-Pad6)") (class "Default")
      (node (ref "U21") (pin "6") (pinfunction "NC_6") (pintype "no_connect"))
    )
    (net (code "97") (name "unconnected-(U22-NC-Pad2)") (class "Default")
      (node (ref "U22") (pin "2") (pinfunction "NC_2") (pintype "passive"))
    )
    (net (code "98") (name "unconnected-(U22-PG-Pad3)") (class "Default")
      (node (ref "U22") (pin "3") (pinfunction "PG_3") (pintype "output"))
    )
  )
)
